# PCB-E21-CMB6_v03-17.net
KiCad netlist of a schematic drawn in EAGLE
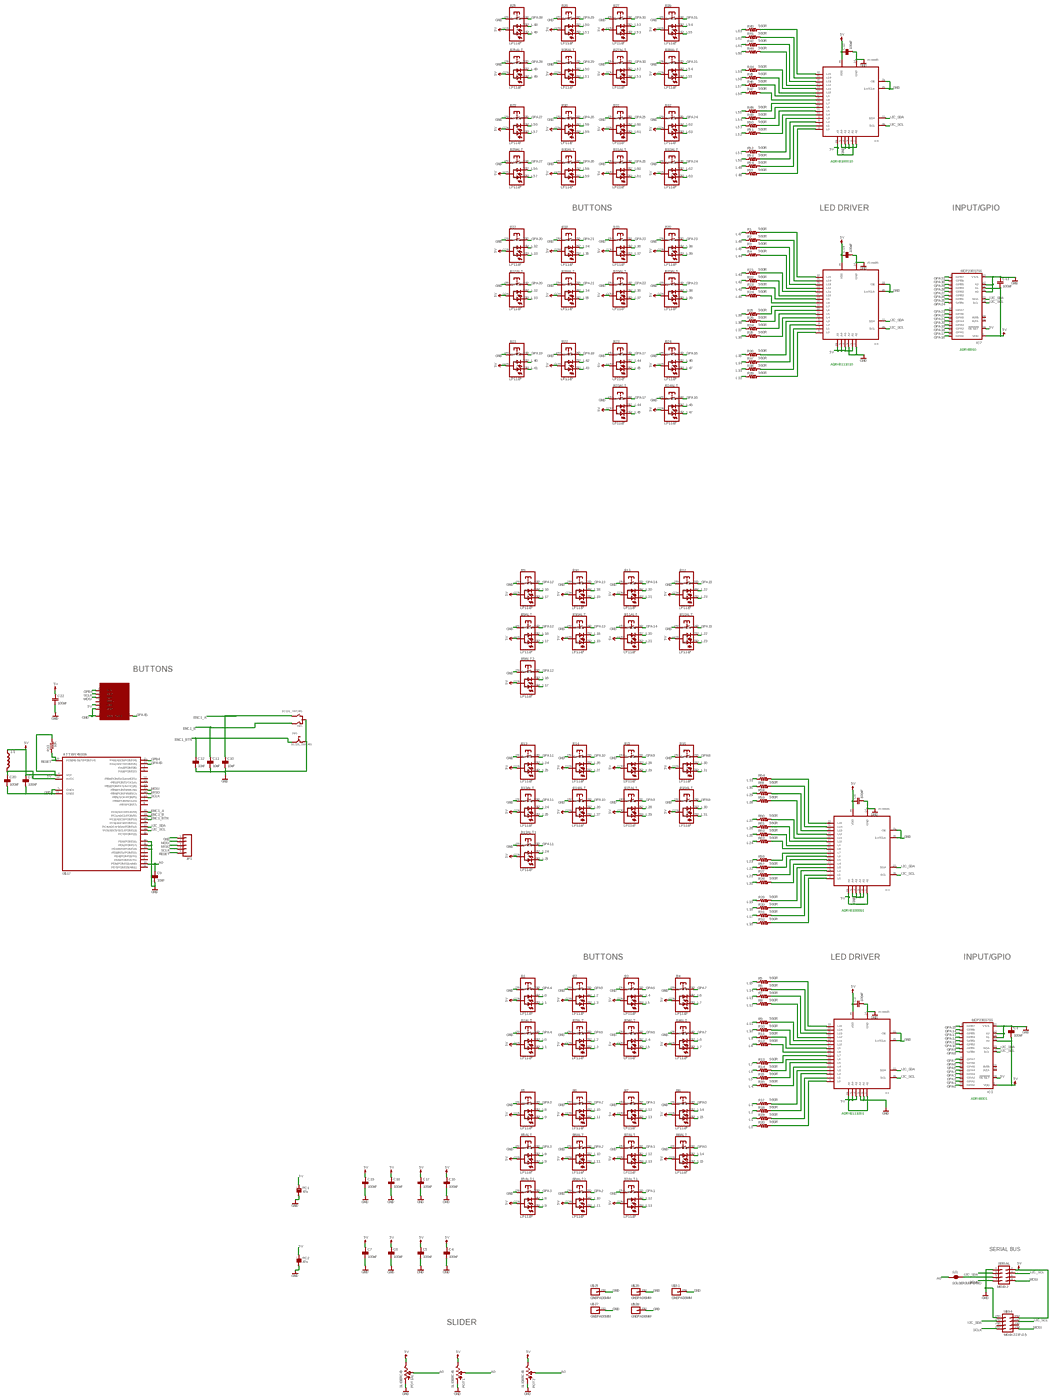
[diagram p0: schematic, sheet 1, overview]
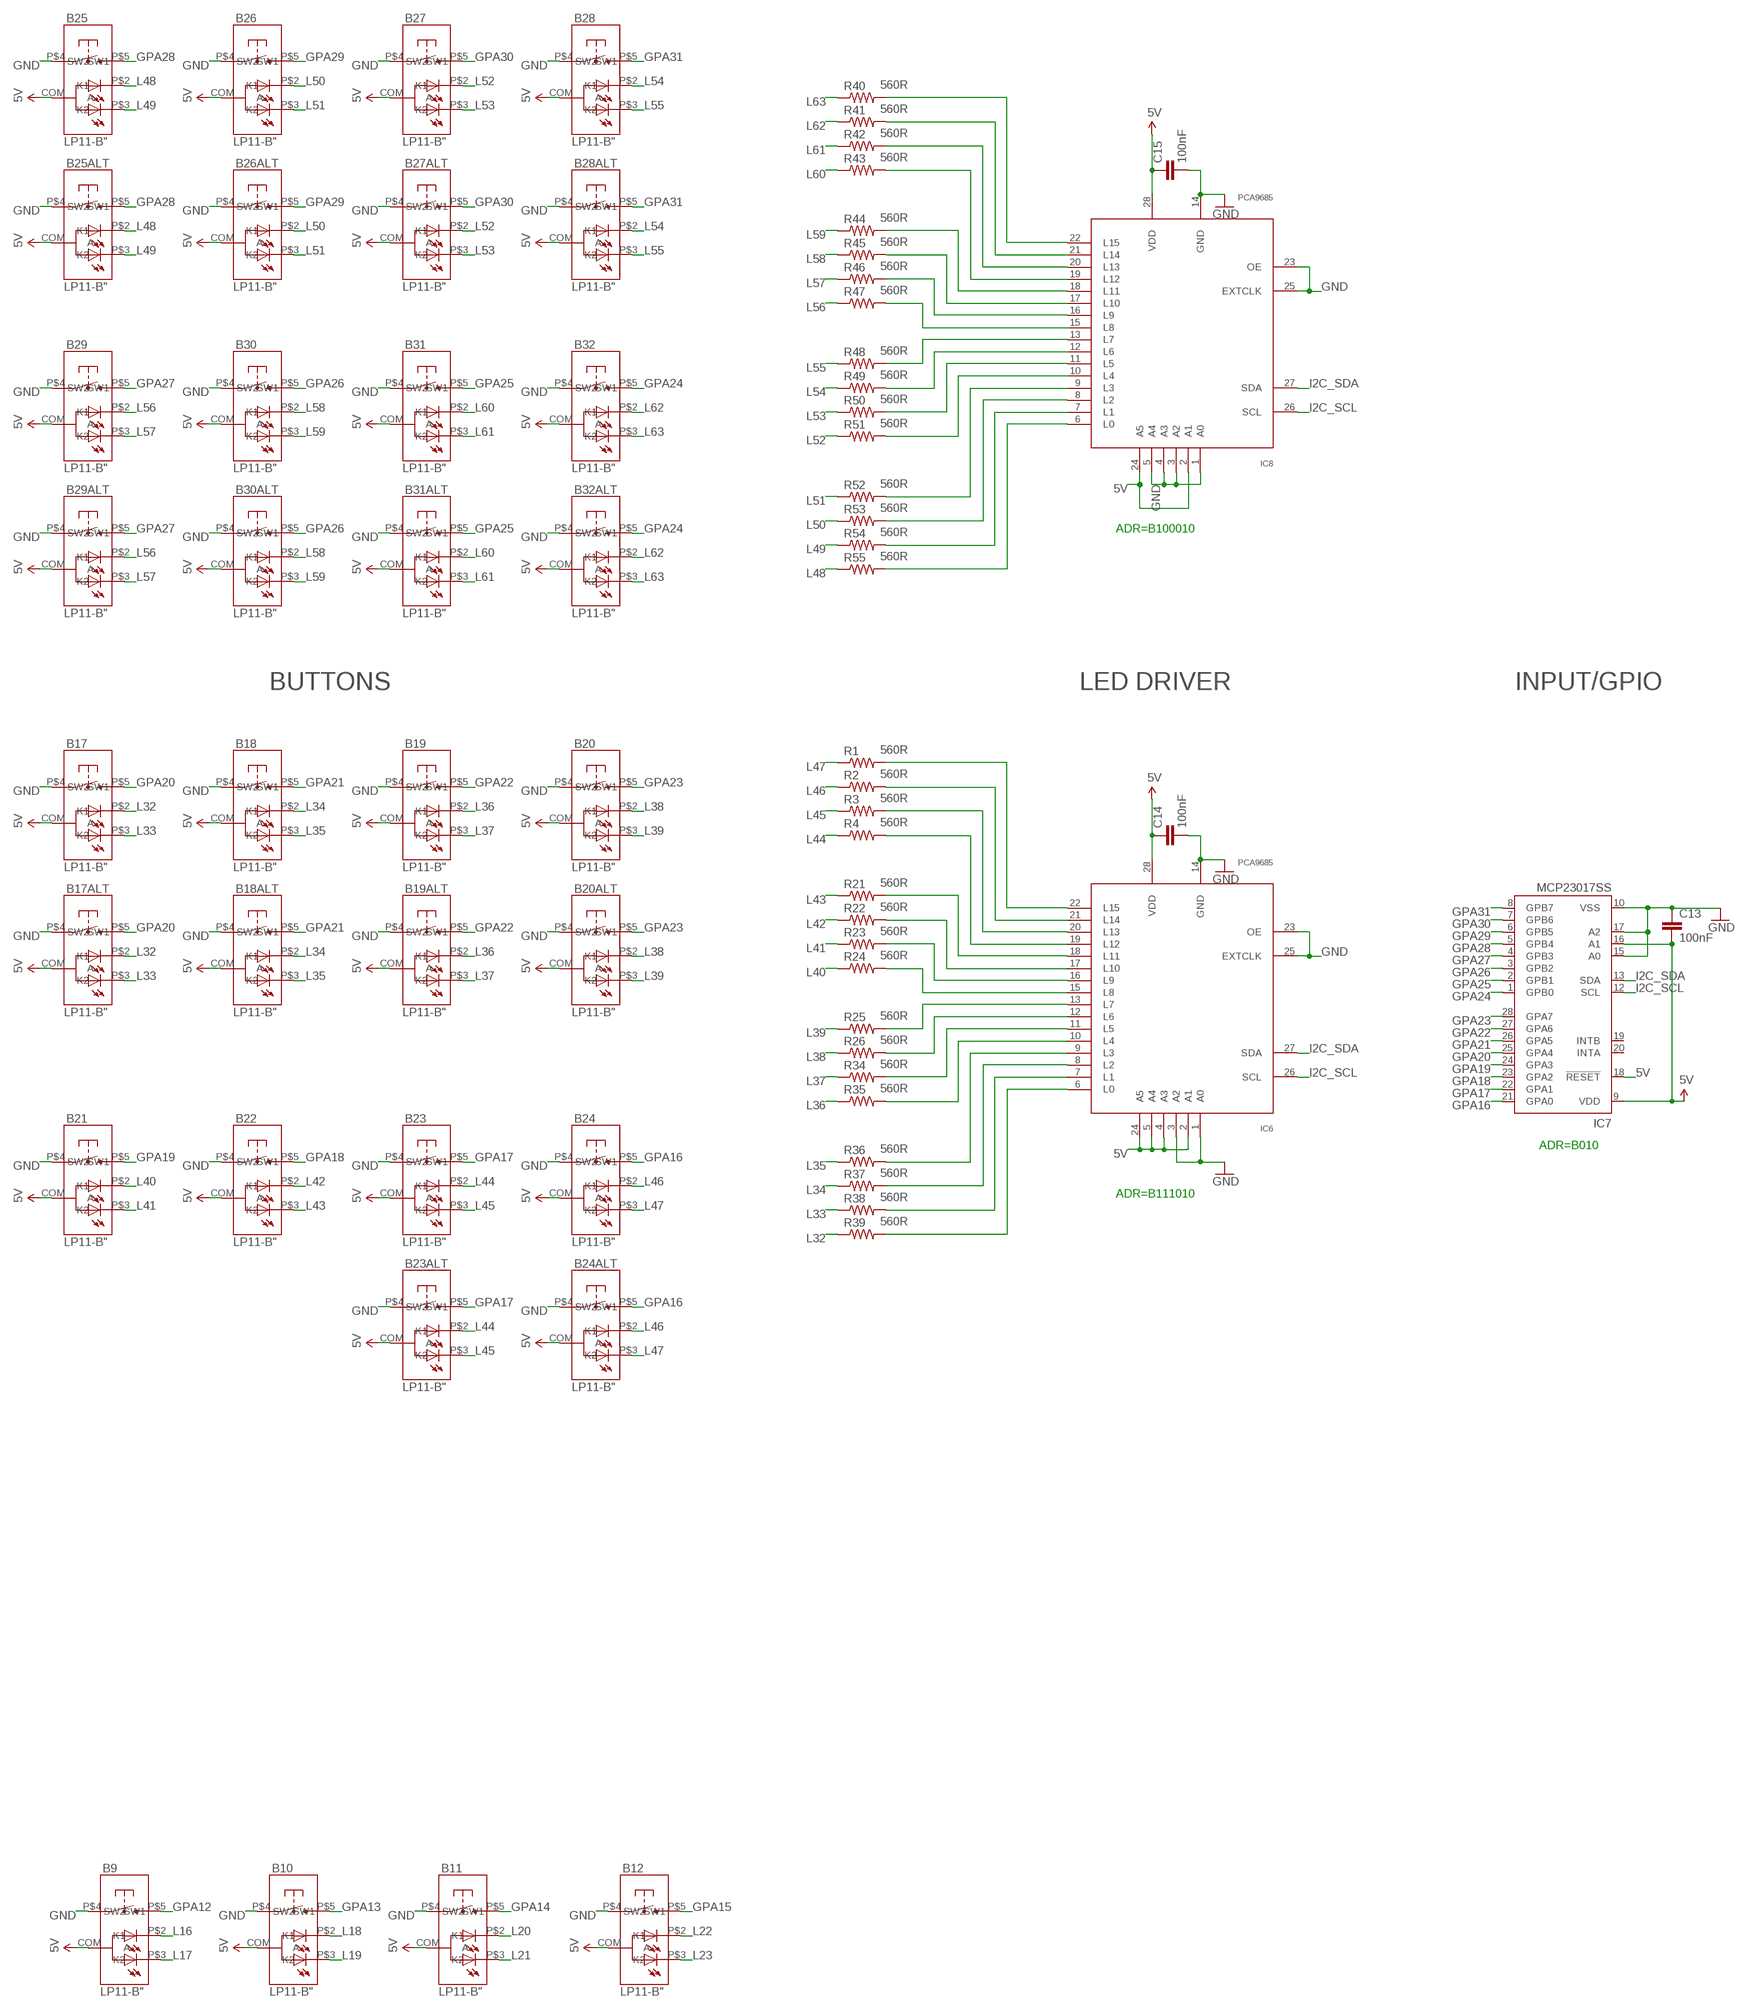
[diagram p1: schematic, sheet 1, part 1 of 5]
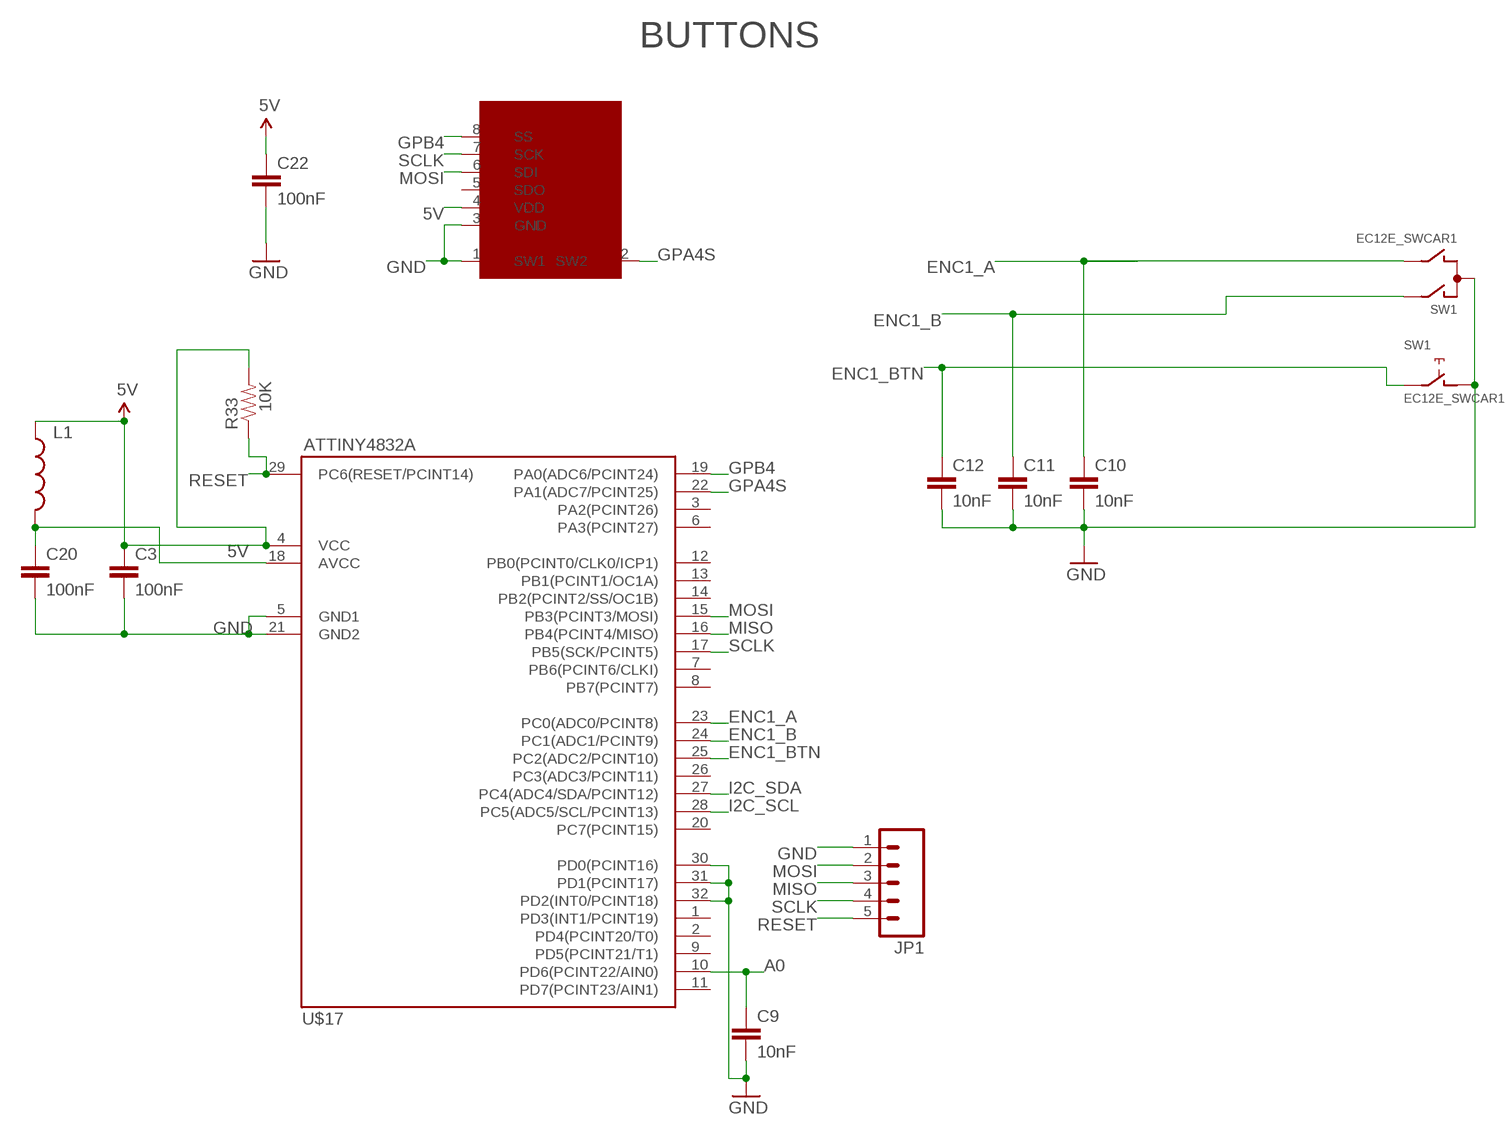
[diagram p2: schematic, sheet 1, part 2 of 5]
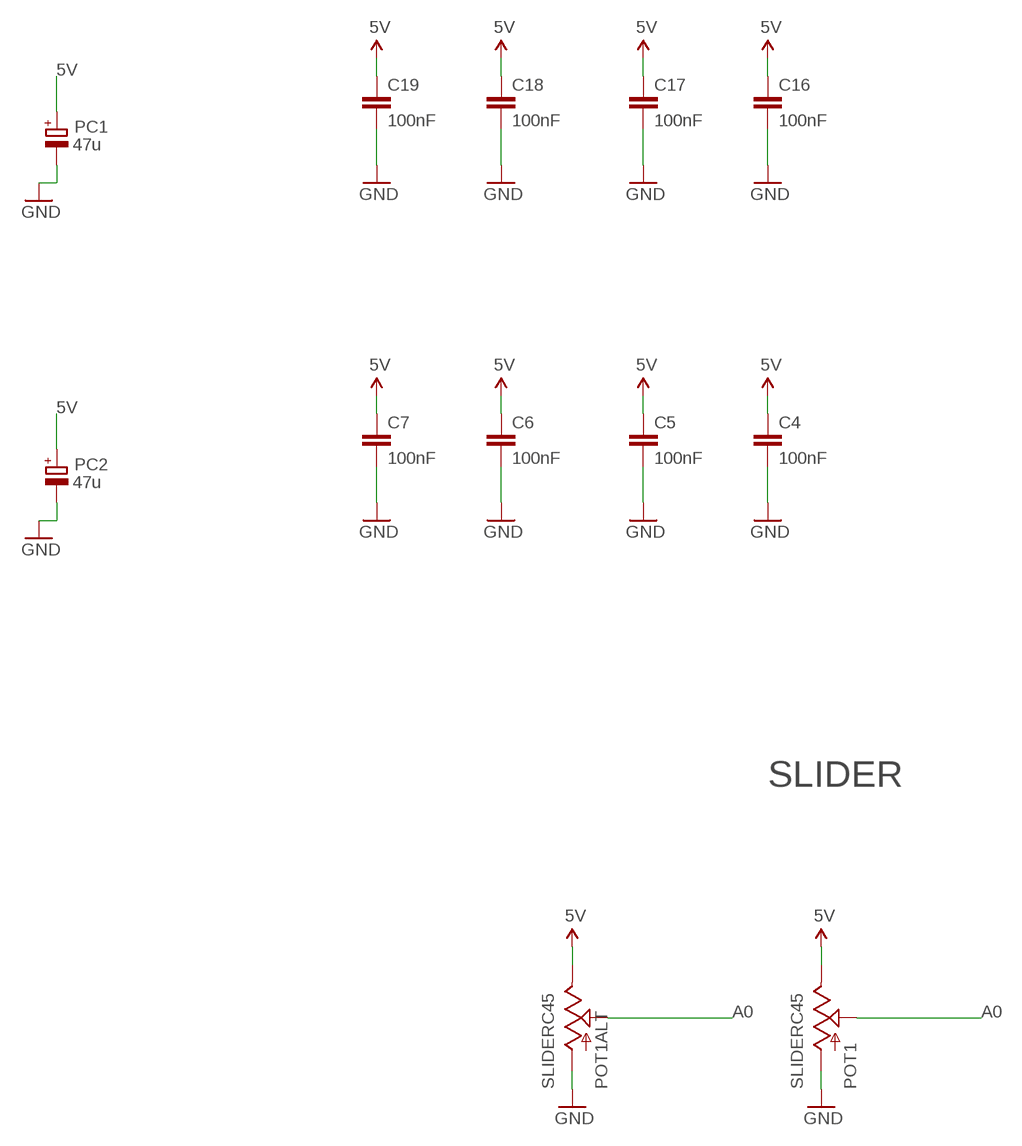
[diagram p3: schematic, sheet 1, part 3 of 5]
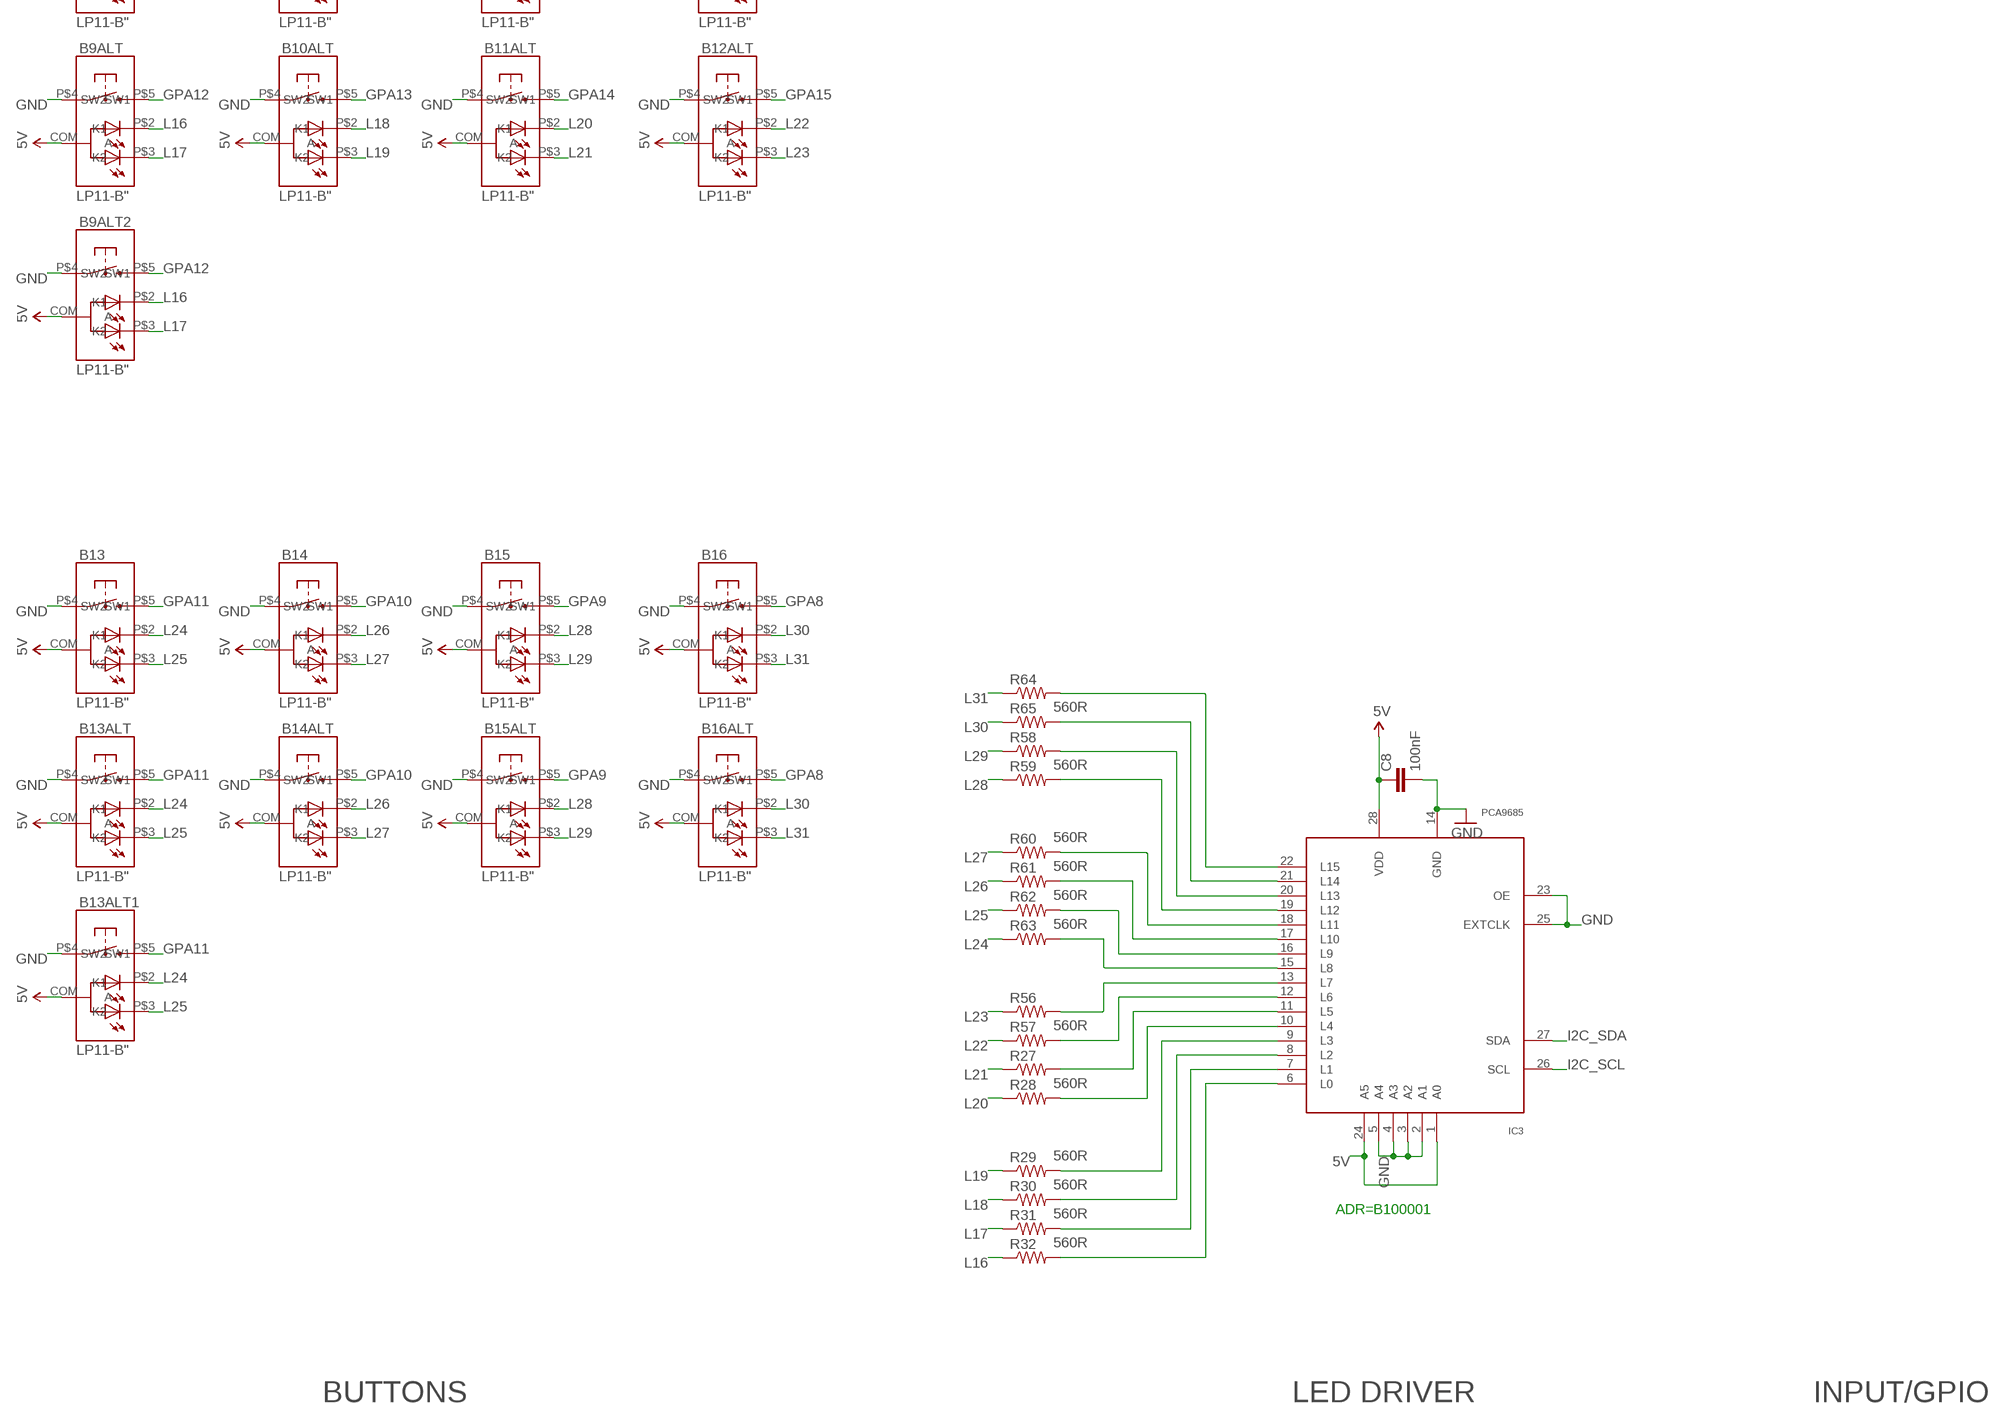
[diagram p4: schematic, sheet 1, part 4 of 5]
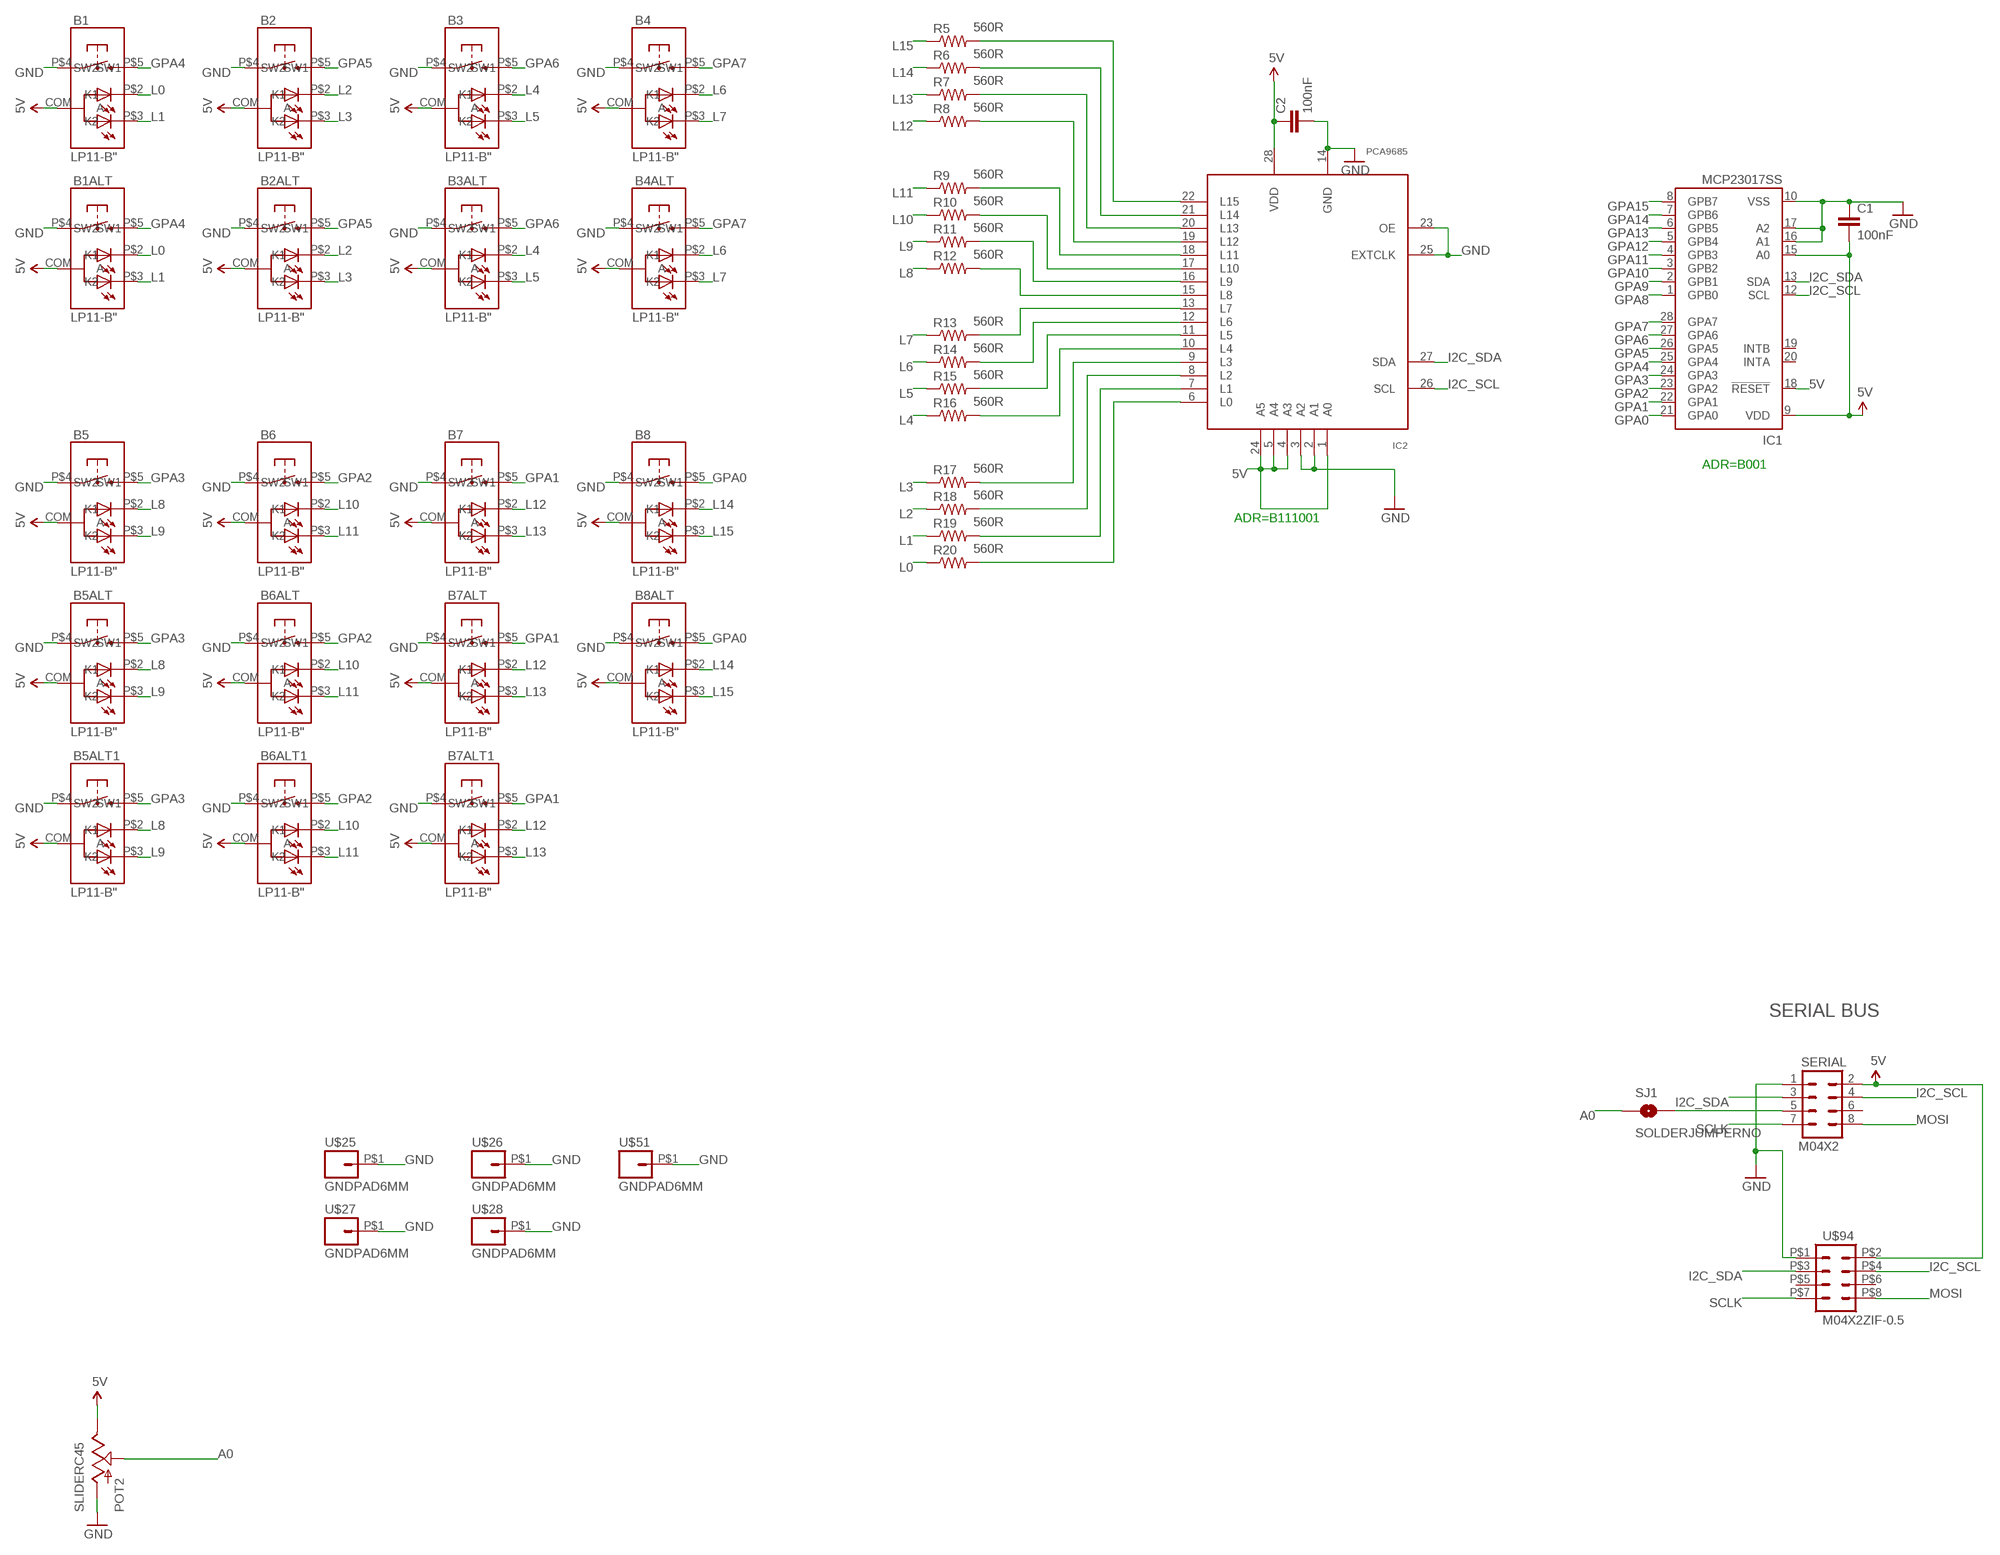
[diagram p5: schematic, sheet 1, part 5 of 5]

(export (version "E")
  (design (tool "Eeschema 10.0.6"))
  (components
    (comp (ref "B1")
      (value "LP11-B\"")
      (footprint "eagle-import:LP11")
      (libsource (lib "eagle-import") (part "LP11-B{dblquote}"))
    )
    (comp (ref "B1ALT")
      (value "LP11-B\"")
      (footprint "eagle-import:LP11")
      (libsource (lib "eagle-import") (part "LP11-B{dblquote}"))
    )
    (comp (ref "B2")
      (value "LP11-B\"")
      (footprint "eagle-import:LP11")
      (libsource (lib "eagle-import") (part "LP11-B{dblquote}"))
    )
    (comp (ref "B2ALT")
      (value "LP11-B\"")
      (footprint "eagle-import:LP11")
      (libsource (lib "eagle-import") (part "LP11-B{dblquote}"))
    )
    (comp (ref "B3")
      (value "LP11-B\"")
      (footprint "eagle-import:LP11")
      (libsource (lib "eagle-import") (part "LP11-B{dblquote}"))
    )
    (comp (ref "B3ALT")
      (value "LP11-B\"")
      (footprint "eagle-import:LP11")
      (libsource (lib "eagle-import") (part "LP11-B{dblquote}"))
    )
    (comp (ref "B4")
      (value "LP11-B\"")
      (footprint "eagle-import:LP11")
      (libsource (lib "eagle-import") (part "LP11-B{dblquote}"))
    )
    (comp (ref "B4ALT")
      (value "LP11-B\"")
      (footprint "eagle-import:LP11")
      (libsource (lib "eagle-import") (part "LP11-B{dblquote}"))
    )
    (comp (ref "B5")
      (value "LP11-B\"")
      (footprint "eagle-import:LP11")
      (libsource (lib "eagle-import") (part "LP11-B{dblquote}"))
    )
    (comp (ref "B5ALT")
      (value "LP11-B\"")
      (footprint "eagle-import:LP11")
      (libsource (lib "eagle-import") (part "LP11-B{dblquote}"))
    )
    (comp (ref "B5ALT1")
      (value "LP11-B\"")
      (footprint "eagle-import:LP11")
      (libsource (lib "eagle-import") (part "LP11-B{dblquote}"))
    )
    (comp (ref "B6")
      (value "LP11-B\"")
      (footprint "eagle-import:LP11")
      (libsource (lib "eagle-import") (part "LP11-B{dblquote}"))
    )
    (comp (ref "B6ALT")
      (value "LP11-B\"")
      (footprint "eagle-import:LP11")
      (libsource (lib "eagle-import") (part "LP11-B{dblquote}"))
    )
    (comp (ref "B6ALT1")
      (value "LP11-B\"")
      (footprint "eagle-import:LP11")
      (libsource (lib "eagle-import") (part "LP11-B{dblquote}"))
    )
    (comp (ref "B7")
      (value "LP11-B\"")
      (footprint "eagle-import:LP11")
      (libsource (lib "eagle-import") (part "LP11-B{dblquote}"))
    )
    (comp (ref "B7ALT")
      (value "LP11-B\"")
      (footprint "eagle-import:LP11")
      (libsource (lib "eagle-import") (part "LP11-B{dblquote}"))
    )
    (comp (ref "B7ALT1")
      (value "LP11-B\"")
      (footprint "eagle-import:LP11")
      (libsource (lib "eagle-import") (part "LP11-B{dblquote}"))
    )
    (comp (ref "B8")
      (value "LP11-B\"")
      (footprint "eagle-import:LP11")
      (libsource (lib "eagle-import") (part "LP11-B{dblquote}"))
    )
    (comp (ref "B8ALT")
      (value "LP11-B\"")
      (footprint "eagle-import:LP11")
      (libsource (lib "eagle-import") (part "LP11-B{dblquote}"))
    )
    (comp (ref "B9")
      (value "LP11-B\"")
      (footprint "eagle-import:LP11")
      (libsource (lib "eagle-import") (part "LP11-B{dblquote}"))
    )
    (comp (ref "B9ALT")
      (value "LP11-B\"")
      (footprint "eagle-import:LP11")
      (libsource (lib "eagle-import") (part "LP11-B{dblquote}"))
    )
    (comp (ref "B9ALT2")
      (value "LP11-B\"")
      (footprint "eagle-import:LP11")
      (libsource (lib "eagle-import") (part "LP11-B{dblquote}"))
    )
    (comp (ref "B10")
      (value "LP11-B\"")
      (footprint "eagle-import:LP11")
      (libsource (lib "eagle-import") (part "LP11-B{dblquote}"))
    )
    (comp (ref "B10ALT")
      (value "LP11-B\"")
      (footprint "eagle-import:LP11")
      (libsource (lib "eagle-import") (part "LP11-B{dblquote}"))
    )
    (comp (ref "B11")
      (value "LP11-B\"")
      (footprint "eagle-import:LP11")
      (libsource (lib "eagle-import") (part "LP11-B{dblquote}"))
    )
    (comp (ref "B11ALT")
      (value "LP11-B\"")
      (footprint "eagle-import:LP11")
      (libsource (lib "eagle-import") (part "LP11-B{dblquote}"))
    )
    (comp (ref "B12")
      (value "LP11-B\"")
      (footprint "eagle-import:LP11")
      (libsource (lib "eagle-import") (part "LP11-B{dblquote}"))
    )
    (comp (ref "B12ALT")
      (value "LP11-B\"")
      (footprint "eagle-import:LP11")
      (libsource (lib "eagle-import") (part "LP11-B{dblquote}"))
    )
    (comp (ref "B13")
      (value "LP11-B\"")
      (footprint "eagle-import:LP11")
      (libsource (lib "eagle-import") (part "LP11-B{dblquote}"))
    )
    (comp (ref "B13ALT")
      (value "LP11-B\"")
      (footprint "eagle-import:LP11")
      (libsource (lib "eagle-import") (part "LP11-B{dblquote}"))
    )
    (comp (ref "B13ALT1")
      (value "LP11-B\"")
      (footprint "eagle-import:LP11")
      (libsource (lib "eagle-import") (part "LP11-B{dblquote}"))
    )
    (comp (ref "B14")
      (value "LP11-B\"")
      (footprint "eagle-import:LP11")
      (libsource (lib "eagle-import") (part "LP11-B{dblquote}"))
    )
    (comp (ref "B14ALT")
      (value "LP11-B\"")
      (footprint "eagle-import:LP11")
      (libsource (lib "eagle-import") (part "LP11-B{dblquote}"))
    )
    (comp (ref "B15")
      (value "LP11-B\"")
      (footprint "eagle-import:LP11")
      (libsource (lib "eagle-import") (part "LP11-B{dblquote}"))
    )
    (comp (ref "B15ALT")
      (value "LP11-B\"")
      (footprint "eagle-import:LP11")
      (libsource (lib "eagle-import") (part "LP11-B{dblquote}"))
    )
    (comp (ref "B16")
      (value "LP11-B\"")
      (footprint "eagle-import:LP11")
      (libsource (lib "eagle-import") (part "LP11-B{dblquote}"))
    )
    (comp (ref "B16ALT")
      (value "LP11-B\"")
      (footprint "eagle-import:LP11")
      (libsource (lib "eagle-import") (part "LP11-B{dblquote}"))
    )
    (comp (ref "B17")
      (value "LP11-B\"")
      (footprint "eagle-import:LP11")
      (libsource (lib "eagle-import") (part "LP11-B{dblquote}"))
    )
    (comp (ref "B17ALT")
      (value "LP11-B\"")
      (footprint "eagle-import:LP11")
      (libsource (lib "eagle-import") (part "LP11-B{dblquote}"))
    )
    (comp (ref "B18")
      (value "LP11-B\"")
      (footprint "eagle-import:LP11")
      (libsource (lib "eagle-import") (part "LP11-B{dblquote}"))
    )
    (comp (ref "B18ALT")
      (value "LP11-B\"")
      (footprint "eagle-import:LP11")
      (libsource (lib "eagle-import") (part "LP11-B{dblquote}"))
    )
    (comp (ref "B19")
      (value "LP11-B\"")
      (footprint "eagle-import:LP11")
      (libsource (lib "eagle-import") (part "LP11-B{dblquote}"))
    )
    (comp (ref "B19ALT")
      (value "LP11-B\"")
      (footprint "eagle-import:LP11")
      (libsource (lib "eagle-import") (part "LP11-B{dblquote}"))
    )
    (comp (ref "B20")
      (value "LP11-B\"")
      (footprint "eagle-import:LP11")
      (libsource (lib "eagle-import") (part "LP11-B{dblquote}"))
    )
    (comp (ref "B20ALT")
      (value "LP11-B\"")
      (footprint "eagle-import:LP11")
      (libsource (lib "eagle-import") (part "LP11-B{dblquote}"))
    )
    (comp (ref "B21")
      (value "LP11-B\"")
      (footprint "eagle-import:LP11")
      (libsource (lib "eagle-import") (part "LP11-B{dblquote}"))
    )
    (comp (ref "B22")
      (value "LP11-B\"")
      (footprint "eagle-import:LP11")
      (libsource (lib "eagle-import") (part "LP11-B{dblquote}"))
    )
    (comp (ref "B23")
      (value "LP11-B\"")
      (footprint "eagle-import:LP11")
      (libsource (lib "eagle-import") (part "LP11-B{dblquote}"))
    )
    (comp (ref "B23ALT")
      (value "LP11-B\"")
      (footprint "eagle-import:LP11")
      (libsource (lib "eagle-import") (part "LP11-B{dblquote}"))
    )
    (comp (ref "B24")
      (value "LP11-B\"")
      (footprint "eagle-import:LP11")
      (libsource (lib "eagle-import") (part "LP11-B{dblquote}"))
    )
    (comp (ref "B24ALT")
      (value "LP11-B\"")
      (footprint "eagle-import:LP11")
      (libsource (lib "eagle-import") (part "LP11-B{dblquote}"))
    )
    (comp (ref "B25")
      (value "LP11-B\"")
      (footprint "eagle-import:LP11")
      (libsource (lib "eagle-import") (part "LP11-B{dblquote}"))
    )
    (comp (ref "B25ALT")
      (value "LP11-B\"")
      (footprint "eagle-import:LP11")
      (libsource (lib "eagle-import") (part "LP11-B{dblquote}"))
    )
    (comp (ref "B26")
      (value "LP11-B\"")
      (footprint "eagle-import:LP11")
      (libsource (lib "eagle-import") (part "LP11-B{dblquote}"))
    )
    (comp (ref "B26ALT")
      (value "LP11-B\"")
      (footprint "eagle-import:LP11")
      (libsource (lib "eagle-import") (part "LP11-B{dblquote}"))
    )
    (comp (ref "B27")
      (value "LP11-B\"")
      (footprint "eagle-import:LP11")
      (libsource (lib "eagle-import") (part "LP11-B{dblquote}"))
    )
    (comp (ref "B27ALT")
      (value "LP11-B\"")
      (footprint "eagle-import:LP11")
      (libsource (lib "eagle-import") (part "LP11-B{dblquote}"))
    )
    (comp (ref "B28")
      (value "LP11-B\"")
      (footprint "eagle-import:LP11")
      (libsource (lib "eagle-import") (part "LP11-B{dblquote}"))
    )
    (comp (ref "B28ALT")
      (value "LP11-B\"")
      (footprint "eagle-import:LP11")
      (libsource (lib "eagle-import") (part "LP11-B{dblquote}"))
    )
    (comp (ref "B29")
      (value "LP11-B\"")
      (footprint "eagle-import:LP11")
      (libsource (lib "eagle-import") (part "LP11-B{dblquote}"))
    )
    (comp (ref "B29ALT")
      (value "LP11-B\"")
      (footprint "eagle-import:LP11")
      (libsource (lib "eagle-import") (part "LP11-B{dblquote}"))
    )
    (comp (ref "B30")
      (value "LP11-B\"")
      (footprint "eagle-import:LP11")
      (libsource (lib "eagle-import") (part "LP11-B{dblquote}"))
    )
    (comp (ref "B30ALT")
      (value "LP11-B\"")
      (footprint "eagle-import:LP11")
      (libsource (lib "eagle-import") (part "LP11-B{dblquote}"))
    )
    (comp (ref "B31")
      (value "LP11-B\"")
      (footprint "eagle-import:LP11")
      (libsource (lib "eagle-import") (part "LP11-B{dblquote}"))
    )
    (comp (ref "B31ALT")
      (value "LP11-B\"")
      (footprint "eagle-import:LP11")
      (libsource (lib "eagle-import") (part "LP11-B{dblquote}"))
    )
    (comp (ref "B32")
      (value "LP11-B\"")
      (footprint "eagle-import:LP11")
      (libsource (lib "eagle-import") (part "LP11-B{dblquote}"))
    )
    (comp (ref "B32ALT")
      (value "LP11-B\"")
      (footprint "eagle-import:LP11")
      (libsource (lib "eagle-import") (part "LP11-B{dblquote}"))
    )
    (comp (ref "C1")
      (value "100nF")
      (footprint "eagle-import:0603-CAP")
      (libsource (lib "eagle-import") (part "CAP0603-CAP"))
    )
    (comp (ref "C2")
      (value "100nF")
      (footprint "eagle-import:0603-CAP")
      (libsource (lib "eagle-import") (part "CAP0603-CAP"))
    )
    (comp (ref "C3")
      (value "100nF")
      (footprint "eagle-import:0603-CAP")
      (libsource (lib "eagle-import") (part "CAP0603-CAP"))
    )
    (comp (ref "C4")
      (value "100nF")
      (footprint "eagle-import:0603-CAP")
      (libsource (lib "eagle-import") (part "CAP0603-CAP"))
    )
    (comp (ref "C5")
      (value "100nF")
      (footprint "eagle-import:0603-CAP")
      (libsource (lib "eagle-import") (part "CAP0603-CAP"))
    )
    (comp (ref "C6")
      (value "100nF")
      (footprint "eagle-import:0603-CAP")
      (libsource (lib "eagle-import") (part "CAP0603-CAP"))
    )
    (comp (ref "C7")
      (value "100nF")
      (footprint "eagle-import:0603-CAP")
      (libsource (lib "eagle-import") (part "CAP0603-CAP"))
    )
    (comp (ref "C8")
      (value "100nF")
      (footprint "eagle-import:0603-CAP")
      (libsource (lib "eagle-import") (part "CAP0603-CAP"))
    )
    (comp (ref "C9")
      (value "10nF")
      (footprint "eagle-import:0603-CAP")
      (libsource (lib "eagle-import") (part "CAP0603-CAP"))
    )
    (comp (ref "C10")
      (value "10nF")
      (footprint "eagle-import:0603-CAP")
      (libsource (lib "eagle-import") (part "CAP0603-CAP"))
    )
    (comp (ref "C11")
      (value "10nF")
      (footprint "eagle-import:0603-CAP")
      (libsource (lib "eagle-import") (part "CAP0603-CAP"))
    )
    (comp (ref "C12")
      (value "10nF")
      (footprint "eagle-import:0603-CAP")
      (libsource (lib "eagle-import") (part "CAP0603-CAP"))
    )
    (comp (ref "C13")
      (value "100nF")
      (footprint "eagle-import:0603-CAP")
      (libsource (lib "eagle-import") (part "CAP0603-CAP"))
    )
    (comp (ref "C14")
      (value "100nF")
      (footprint "eagle-import:0603-CAP")
      (libsource (lib "eagle-import") (part "CAP0603-CAP"))
    )
    (comp (ref "C15")
      (value "100nF")
      (footprint "eagle-import:0603-CAP")
      (libsource (lib "eagle-import") (part "CAP0603-CAP"))
    )
    (comp (ref "C16")
      (value "100nF")
      (footprint "eagle-import:0603-CAP")
      (libsource (lib "eagle-import") (part "CAP0603-CAP"))
    )
    (comp (ref "C17")
      (value "100nF")
      (footprint "eagle-import:0603-CAP")
      (libsource (lib "eagle-import") (part "CAP0603-CAP"))
    )
    (comp (ref "C18")
      (value "100nF")
      (footprint "eagle-import:0603-CAP")
      (libsource (lib "eagle-import") (part "CAP0603-CAP"))
    )
    (comp (ref "C19")
      (value "100nF")
      (footprint "eagle-import:0603-CAP")
      (libsource (lib "eagle-import") (part "CAP0603-CAP"))
    )
    (comp (ref "C20")
      (value "100nF")
      (footprint "eagle-import:0603-CAP")
      (libsource (lib "eagle-import") (part "CAP0603-CAP"))
    )
    (comp (ref "C22")
      (value "100nF")
      (footprint "eagle-import:0603-CAP")
      (libsource (lib "eagle-import") (part "CAP0603-CAP"))
    )
    (comp (ref "IC1")
      (value "MCP23017SS")
      (footprint "eagle-import:SSOP28")
      (fields
        (field (name "MF") "MICROCHIP")
        (field (name "MPN") "MCP23017-E/SS")
        (field (name "MPN_1") "MCP23017-E/SS")
        (field (name "OC_FARNELL") "1467674")
        (field (name "OC_NEWARK") "31K2960")
      )
      (libsource (lib "eagle-import") (part "MCP23017SS"))
    )
    (comp (ref "IC2")
      (value "PCA9685")
      (footprint "eagle-import:TSSOP28")
      (libsource (lib "eagle-import") (part "PCA9685"))
    )
    (comp (ref "IC3")
      (value "PCA9685")
      (footprint "eagle-import:TSSOP28")
      (libsource (lib "eagle-import") (part "PCA9685"))
    )
    (comp (ref "IC6")
      (value "PCA9685")
      (footprint "eagle-import:TSSOP28")
      (libsource (lib "eagle-import") (part "PCA9685"))
    )
    (comp (ref "IC7")
      (value "MCP23017SS")
      (footprint "eagle-import:SSOP28")
      (fields
        (field (name "MF") "MICROCHIP")
        (field (name "MPN") "MCP23017-E/SS")
        (field (name "MPN_1") "MCP23017-E/SS")
        (field (name "OC_FARNELL") "1467674")
        (field (name "OC_NEWARK") "31K2960")
      )
      (libsource (lib "eagle-import") (part "MCP23017SS"))
    )
    (comp (ref "IC8")
      (value "PCA9685")
      (footprint "eagle-import:TSSOP28")
      (libsource (lib "eagle-import") (part "PCA9685"))
    )
    (comp (ref "JP1")
      (value "M051.27MM")
      (footprint "eagle-import:1X05-1.27MM")
      (libsource (lib "eagle-import") (part "M051.27MM"))
    )
    (comp (ref "L1")
      (value "INDUCTOR0805")
      (footprint "eagle-import:0805")
      (libsource (lib "eagle-import") (part "INDUCTOR0805"))
    )
    (comp (ref "PC1")
      (value "47u")
      (footprint "eagle-import:PANASONIC_D")
      (libsource (lib "eagle-import") (part "CPOL-EUD"))
    )
    (comp (ref "PC2")
      (value "47u")
      (footprint "eagle-import:PANASONIC_D")
      (libsource (lib "eagle-import") (part "CPOL-EUD"))
    )
    (comp (ref "POT1")
      (value "SLIDERC45")
      (footprint "eagle-import:SLIDER45-CAR1")
      (libsource (lib "eagle-import") (part "SLIDERC45"))
    )
    (comp (ref "POT1ALT")
      (value "SLIDERC45")
      (footprint "eagle-import:SLIDER45-CAR1")
      (libsource (lib "eagle-import") (part "SLIDERC45"))
    )
    (comp (ref "POT2")
      (value "SLIDERC45")
      (footprint "eagle-import:SLIDER45-CAR1")
      (libsource (lib "eagle-import") (part "SLIDERC45"))
    )
    (comp (ref "R1")
      (value "560R")
      (footprint "eagle-import:0603-RES")
      (libsource (lib "eagle-import") (part "RESISTOR0603-RES"))
    )
    (comp (ref "R2")
      (value "560R")
      (footprint "eagle-import:0603-RES")
      (libsource (lib "eagle-import") (part "RESISTOR0603-RES"))
    )
    (comp (ref "R3")
      (value "560R")
      (footprint "eagle-import:0603-RES")
      (libsource (lib "eagle-import") (part "RESISTOR0603-RES"))
    )
    (comp (ref "R4")
      (value "560R")
      (footprint "eagle-import:0603-RES")
      (libsource (lib "eagle-import") (part "RESISTOR0603-RES"))
    )
    (comp (ref "R5")
      (value "560R")
      (footprint "eagle-import:0603-RES")
      (libsource (lib "eagle-import") (part "RESISTOR0603-RES"))
    )
    (comp (ref "R6")
      (value "560R")
      (footprint "eagle-import:0603-RES")
      (libsource (lib "eagle-import") (part "RESISTOR0603-RES"))
    )
    (comp (ref "R7")
      (value "560R")
      (footprint "eagle-import:0603-RES")
      (libsource (lib "eagle-import") (part "RESISTOR0603-RES"))
    )
    (comp (ref "R8")
      (value "560R")
      (footprint "eagle-import:0603-RES")
      (libsource (lib "eagle-import") (part "RESISTOR0603-RES"))
    )
    (comp (ref "R9")
      (value "560R")
      (footprint "eagle-import:0603-RES")
      (libsource (lib "eagle-import") (part "RESISTOR0603-RES"))
    )
    (comp (ref "R10")
      (value "560R")
      (footprint "eagle-import:0603-RES")
      (libsource (lib "eagle-import") (part "RESISTOR0603-RES"))
    )
    (comp (ref "R11")
      (value "560R")
      (footprint "eagle-import:0603-RES")
      (libsource (lib "eagle-import") (part "RESISTOR0603-RES"))
    )
    (comp (ref "R12")
      (value "560R")
      (footprint "eagle-import:0603-RES")
      (libsource (lib "eagle-import") (part "RESISTOR0603-RES"))
    )
    (comp (ref "R13")
      (value "560R")
      (footprint "eagle-import:0603-RES")
      (libsource (lib "eagle-import") (part "RESISTOR0603-RES"))
    )
    (comp (ref "R14")
      (value "560R")
      (footprint "eagle-import:0603-RES")
      (libsource (lib "eagle-import") (part "RESISTOR0603-RES"))
    )
    (comp (ref "R15")
      (value "560R")
      (footprint "eagle-import:0603-RES")
      (libsource (lib "eagle-import") (part "RESISTOR0603-RES"))
    )
    (comp (ref "R16")
      (value "560R")
      (footprint "eagle-import:0603-RES")
      (libsource (lib "eagle-import") (part "RESISTOR0603-RES"))
    )
    (comp (ref "R17")
      (value "560R")
      (footprint "eagle-import:0603-RES")
      (libsource (lib "eagle-import") (part "RESISTOR0603-RES"))
    )
    (comp (ref "R18")
      (value "560R")
      (footprint "eagle-import:0603-RES")
      (libsource (lib "eagle-import") (part "RESISTOR0603-RES"))
    )
    (comp (ref "R19")
      (value "560R")
      (footprint "eagle-import:0603-RES")
      (libsource (lib "eagle-import") (part "RESISTOR0603-RES"))
    )
    (comp (ref "R20")
      (value "560R")
      (footprint "eagle-import:0603-RES")
      (libsource (lib "eagle-import") (part "RESISTOR0603-RES"))
    )
    (comp (ref "R21")
      (value "560R")
      (footprint "eagle-import:0603-RES")
      (libsource (lib "eagle-import") (part "RESISTOR0603-RES"))
    )
    (comp (ref "R22")
      (value "560R")
      (footprint "eagle-import:0603-RES")
      (libsource (lib "eagle-import") (part "RESISTOR0603-RES"))
    )
    (comp (ref "R23")
      (value "560R")
      (footprint "eagle-import:0603-RES")
      (libsource (lib "eagle-import") (part "RESISTOR0603-RES"))
    )
    (comp (ref "R24")
      (value "560R")
      (footprint "eagle-import:0603-RES")
      (libsource (lib "eagle-import") (part "RESISTOR0603-RES"))
    )
    (comp (ref "R25")
      (value "560R")
      (footprint "eagle-import:0603-RES")
      (libsource (lib "eagle-import") (part "RESISTOR0603-RES"))
    )
    (comp (ref "R26")
      (value "560R")
      (footprint "eagle-import:0603-RES")
      (libsource (lib "eagle-import") (part "RESISTOR0603-RES"))
    )
    (comp (ref "R27")
      (value "560R")
      (footprint "eagle-import:0603-RES")
      (libsource (lib "eagle-import") (part "RESISTOR0603-RES"))
    )
    (comp (ref "R28")
      (value "560R")
      (footprint "eagle-import:0603-RES")
      (libsource (lib "eagle-import") (part "RESISTOR0603-RES"))
    )
    (comp (ref "R29")
      (value "560R")
      (footprint "eagle-import:0603-RES")
      (libsource (lib "eagle-import") (part "RESISTOR0603-RES"))
    )
    (comp (ref "R30")
      (value "560R")
      (footprint "eagle-import:0603-RES")
      (libsource (lib "eagle-import") (part "RESISTOR0603-RES"))
    )
    (comp (ref "R31")
      (value "560R")
      (footprint "eagle-import:0603-RES")
      (libsource (lib "eagle-import") (part "RESISTOR0603-RES"))
    )
    (comp (ref "R32")
      (value "560R")
      (footprint "eagle-import:0603-RES")
      (libsource (lib "eagle-import") (part "RESISTOR0603-RES"))
    )
    (comp (ref "R33")
      (value "10K")
      (footprint "eagle-import:0603-RES")
      (libsource (lib "eagle-import") (part "RESISTOR0603-RES"))
    )
    (comp (ref "R34")
      (value "560R")
      (footprint "eagle-import:0603-RES")
      (libsource (lib "eagle-import") (part "RESISTOR0603-RES"))
    )
    (comp (ref "R35")
      (value "560R")
      (footprint "eagle-import:0603-RES")
      (libsource (lib "eagle-import") (part "RESISTOR0603-RES"))
    )
    (comp (ref "R36")
      (value "560R")
      (footprint "eagle-import:0603-RES")
      (libsource (lib "eagle-import") (part "RESISTOR0603-RES"))
    )
    (comp (ref "R37")
      (value "560R")
      (footprint "eagle-import:0603-RES")
      (libsource (lib "eagle-import") (part "RESISTOR0603-RES"))
    )
    (comp (ref "R38")
      (value "560R")
      (footprint "eagle-import:0603-RES")
      (libsource (lib "eagle-import") (part "RESISTOR0603-RES"))
    )
    (comp (ref "R39")
      (value "560R")
      (footprint "eagle-import:0603-RES")
      (libsource (lib "eagle-import") (part "RESISTOR0603-RES"))
    )
    (comp (ref "R40")
      (value "560R")
      (footprint "eagle-import:0603-RES")
      (libsource (lib "eagle-import") (part "RESISTOR0603-RES"))
    )
    (comp (ref "R41")
      (value "560R")
      (footprint "eagle-import:0603-RES")
      (libsource (lib "eagle-import") (part "RESISTOR0603-RES"))
    )
    (comp (ref "R42")
      (value "560R")
      (footprint "eagle-import:0603-RES")
      (libsource (lib "eagle-import") (part "RESISTOR0603-RES"))
    )
    (comp (ref "R43")
      (value "560R")
      (footprint "eagle-import:0603-RES")
      (libsource (lib "eagle-import") (part "RESISTOR0603-RES"))
    )
    (comp (ref "R44")
      (value "560R")
      (footprint "eagle-import:0603-RES")
      (libsource (lib "eagle-import") (part "RESISTOR0603-RES"))
    )
    (comp (ref "R45")
      (value "560R")
      (footprint "eagle-import:0603-RES")
      (libsource (lib "eagle-import") (part "RESISTOR0603-RES"))
    )
    (comp (ref "R46")
      (value "560R")
      (footprint "eagle-import:0603-RES")
      (libsource (lib "eagle-import") (part "RESISTOR0603-RES"))
    )
    (comp (ref "R47")
      (value "560R")
      (footprint "eagle-import:0603-RES")
      (libsource (lib "eagle-import") (part "RESISTOR0603-RES"))
    )
    (comp (ref "R48")
      (value "560R")
      (footprint "eagle-import:0603-RES")
      (libsource (lib "eagle-import") (part "RESISTOR0603-RES"))
    )
    (comp (ref "R49")
      (value "560R")
      (footprint "eagle-import:0603-RES")
      (libsource (lib "eagle-import") (part "RESISTOR0603-RES"))
    )
    (comp (ref "R50")
      (value "560R")
      (footprint "eagle-import:0603-RES")
      (libsource (lib "eagle-import") (part "RESISTOR0603-RES"))
    )
    (comp (ref "R51")
      (value "560R")
      (footprint "eagle-import:0603-RES")
      (libsource (lib "eagle-import") (part "RESISTOR0603-RES"))
    )
    (comp (ref "R52")
      (value "560R")
      (footprint "eagle-import:0603-RES")
      (libsource (lib "eagle-import") (part "RESISTOR0603-RES"))
    )
    (comp (ref "R53")
      (value "560R")
      (footprint "eagle-import:0603-RES")
      (libsource (lib "eagle-import") (part "RESISTOR0603-RES"))
    )
    (comp (ref "R54")
      (value "560R")
      (footprint "eagle-import:0603-RES")
      (libsource (lib "eagle-import") (part "RESISTOR0603-RES"))
    )
    (comp (ref "R55")
      (value "560R")
      (footprint "eagle-import:0603-RES")
      (libsource (lib "eagle-import") (part "RESISTOR0603-RES"))
    )
    (comp (ref "R56")
      (value "560R")
      (footprint "eagle-import:0603-RES")
      (libsource (lib "eagle-import") (part "RESISTOR0603-RES"))
    )
    (comp (ref "R57")
      (value "560R")
      (footprint "eagle-import:0603-RES")
      (libsource (lib "eagle-import") (part "RESISTOR0603-RES"))
    )
    (comp (ref "R58")
      (value "560R")
      (footprint "eagle-import:0603-RES")
      (libsource (lib "eagle-import") (part "RESISTOR0603-RES"))
    )
    (comp (ref "R59")
      (value "560R")
      (footprint "eagle-import:0603-RES")
      (libsource (lib "eagle-import") (part "RESISTOR0603-RES"))
    )
    (comp (ref "R60")
      (value "560R")
      (footprint "eagle-import:0603-RES")
      (libsource (lib "eagle-import") (part "RESISTOR0603-RES"))
    )
    (comp (ref "R61")
      (value "560R")
      (footprint "eagle-import:0603-RES")
      (libsource (lib "eagle-import") (part "RESISTOR0603-RES"))
    )
    (comp (ref "R62")
      (value "560R")
      (footprint "eagle-import:0603-RES")
      (libsource (lib "eagle-import") (part "RESISTOR0603-RES"))
    )
    (comp (ref "R63")
      (value "560R")
      (footprint "eagle-import:0603-RES")
      (libsource (lib "eagle-import") (part "RESISTOR0603-RES"))
    )
    (comp (ref "R64")
      (value "560R")
      (footprint "eagle-import:0603-RES")
      (libsource (lib "eagle-import") (part "RESISTOR0603-RES"))
    )
    (comp (ref "R65")
      (value "560R")
      (footprint "eagle-import:0603-RES")
      (libsource (lib "eagle-import") (part "RESISTOR0603-RES"))
    )
    (comp (ref "SERIAL")
      (value "M04X2")
      (footprint "eagle-import:2X4")
      (libsource (lib "eagle-import") (part "SparkFun_M04X2"))
    )
    (comp (ref "SJ1")
      (value "SOLDERJUMPERNO")
      (footprint "eagle-import:SJ_2S-NO")
      (libsource (lib "eagle-import") (part "SOLDERJUMPERNO"))
    )
    (comp (ref "SSW1")
      (value "SMART_SWITCHSMART_SWITCH_8PIN")
      (footprint "eagle-import:SMART_SWITCH")
      (libsource (lib "eagle-import") (part "SMART_SWITCHSMART_SWITCH_8PIN"))
    )
    (comp (ref "SW1")
      (value "EC12E_SWCAR1")
      (footprint "eagle-import:ALPS_EC12E_SW-CAR1")
      (libsource (lib "eagle-import") (part "EC12E_SWCAR1"))
    )
    (comp (ref "U$17")
      (value "ATTINY4832A")
      (footprint "eagle-import:TQFP32-08")
      (libsource (lib "eagle-import") (part "ATTINY4832A"))
    )
    (comp (ref "U$25")
      (value "GNDPAD6MM")
      (footprint "eagle-import:3.2MMPAD6MM")
      (libsource (lib "eagle-import") (part "GNDPAD6MM"))
    )
    (comp (ref "U$26")
      (value "GNDPAD6MM")
      (footprint "eagle-import:3.2MMPAD6MM")
      (libsource (lib "eagle-import") (part "GNDPAD6MM"))
    )
    (comp (ref "U$27")
      (value "GNDPAD6MM")
      (footprint "eagle-import:3.2MMPAD6MM")
      (libsource (lib "eagle-import") (part "GNDPAD6MM"))
    )
    (comp (ref "U$28")
      (value "GNDPAD6MM")
      (footprint "eagle-import:3.2MMPAD6MM")
      (libsource (lib "eagle-import") (part "GNDPAD6MM"))
    )
    (comp (ref "U$51")
      (value "GNDPAD6MM")
      (footprint "eagle-import:3.2MMPAD6MM")
      (libsource (lib "eagle-import") (part "GNDPAD6MM"))
    )
    (comp (ref "U$94")
      (value "M04X2ZIF-0.5")
      (footprint "eagle-import:ZIP-8-0.5")
      (libsource (lib "eagle-import") (part "M04X2ZIF-0.5"))
    )
  )
  (nets
    (net (code "1") (name "5V") (class "Default")
      (node (ref "B1") (pin "COM") (pinfunction "A_COM") (pintype "bidirectional"))
      (node (ref "B10") (pin "COM") (pinfunction "A_COM") (pintype "bidirectional"))
      (node (ref "B10ALT") (pin "COM") (pinfunction "A_COM") (pintype "bidirectional"))
      (node (ref "B11") (pin "COM") (pinfunction "A_COM") (pintype "bidirectional"))
      (node (ref "B11ALT") (pin "COM") (pinfunction "A_COM") (pintype "bidirectional"))
      (node (ref "B12") (pin "COM") (pinfunction "A_COM") (pintype "bidirectional"))
      (node (ref "B12ALT") (pin "COM") (pinfunction "A_COM") (pintype "bidirectional"))
      (node (ref "B13") (pin "COM") (pinfunction "A_COM") (pintype "bidirectional"))
      (node (ref "B13ALT") (pin "COM") (pinfunction "A_COM") (pintype "bidirectional"))
      (node (ref "B13ALT1") (pin "COM") (pinfunction "A_COM") (pintype "bidirectional"))
      (node (ref "B14") (pin "COM") (pinfunction "A_COM") (pintype "bidirectional"))
      (node (ref "B14ALT") (pin "COM") (pinfunction "A_COM") (pintype "bidirectional"))
      (node (ref "B15") (pin "COM") (pinfunction "A_COM") (pintype "bidirectional"))
      (node (ref "B15ALT") (pin "COM") (pinfunction "A_COM") (pintype "bidirectional"))
      (node (ref "B16") (pin "COM") (pinfunction "A_COM") (pintype "bidirectional"))
      (node (ref "B16ALT") (pin "COM") (pinfunction "A_COM") (pintype "bidirectional"))
      (node (ref "B17") (pin "COM") (pinfunction "A_COM") (pintype "bidirectional"))
      (node (ref "B17ALT") (pin "COM") (pinfunction "A_COM") (pintype "bidirectional"))
      (node (ref "B18") (pin "COM") (pinfunction "A_COM") (pintype "bidirectional"))
      (node (ref "B18ALT") (pin "COM") (pinfunction "A_COM") (pintype "bidirectional"))
      (node (ref "B19") (pin "COM") (pinfunction "A_COM") (pintype "bidirectional"))
      (node (ref "B19ALT") (pin "COM") (pinfunction "A_COM") (pintype "bidirectional"))
      (node (ref "B1ALT") (pin "COM") (pinfunction "A_COM") (pintype "bidirectional"))
      (node (ref "B2") (pin "COM") (pinfunction "A_COM") (pintype "bidirectional"))
      (node (ref "B20") (pin "COM") (pinfunction "A_COM") (pintype "bidirectional"))
      (node (ref "B20ALT") (pin "COM") (pinfunction "A_COM") (pintype "bidirectional"))
      (node (ref "B21") (pin "COM") (pinfunction "A_COM") (pintype "bidirectional"))
      (node (ref "B22") (pin "COM") (pinfunction "A_COM") (pintype "bidirectional"))
      (node (ref "B23") (pin "COM") (pinfunction "A_COM") (pintype "bidirectional"))
      (node (ref "B23ALT") (pin "COM") (pinfunction "A_COM") (pintype "bidirectional"))
      (node (ref "B24") (pin "COM") (pinfunction "A_COM") (pintype "bidirectional"))
      (node (ref "B24ALT") (pin "COM") (pinfunction "A_COM") (pintype "bidirectional"))
      (node (ref "B25") (pin "COM") (pinfunction "A_COM") (pintype "bidirectional"))
      (node (ref "B25ALT") (pin "COM") (pinfunction "A_COM") (pintype "bidirectional"))
      (node (ref "B26") (pin "COM") (pinfunction "A_COM") (pintype "bidirectional"))
      (node (ref "B26ALT") (pin "COM") (pinfunction "A_COM") (pintype "bidirectional"))
      (node (ref "B27") (pin "COM") (pinfunction "A_COM") (pintype "bidirectional"))
      (node (ref "B27ALT") (pin "COM") (pinfunction "A_COM") (pintype "bidirectional"))
      (node (ref "B28") (pin "COM") (pinfunction "A_COM") (pintype "bidirectional"))
      (node (ref "B28ALT") (pin "COM") (pinfunction "A_COM") (pintype "bidirectional"))
      (node (ref "B29") (pin "COM") (pinfunction "A_COM") (pintype "bidirectional"))
      (node (ref "B29ALT") (pin "COM") (pinfunction "A_COM") (pintype "bidirectional"))
      (node (ref "B2ALT") (pin "COM") (pinfunction "A_COM") (pintype "bidirectional"))
      (node (ref "B3") (pin "COM") (pinfunction "A_COM") (pintype "bidirectional"))
      (node (ref "B30") (pin "COM") (pinfunction "A_COM") (pintype "bidirectional"))
      (node (ref "B30ALT") (pin "COM") (pinfunction "A_COM") (pintype "bidirectional"))
      (node (ref "B31") (pin "COM") (pinfunction "A_COM") (pintype "bidirectional"))
      (node (ref "B31ALT") (pin "COM") (pinfunction "A_COM") (pintype "bidirectional"))
      (node (ref "B32") (pin "COM") (pinfunction "A_COM") (pintype "bidirectional"))
      (node (ref "B32ALT") (pin "COM") (pinfunction "A_COM") (pintype "bidirectional"))
      (node (ref "B3ALT") (pin "COM") (pinfunction "A_COM") (pintype "bidirectional"))
      (node (ref "B4") (pin "COM") (pinfunction "A_COM") (pintype "bidirectional"))
      (node (ref "B4ALT") (pin "COM") (pinfunction "A_COM") (pintype "bidirectional"))
      (node (ref "B5") (pin "COM") (pinfunction "A_COM") (pintype "bidirectional"))
      (node (ref "B5ALT") (pin "COM") (pinfunction "A_COM") (pintype "bidirectional"))
      (node (ref "B5ALT1") (pin "COM") (pinfunction "A_COM") (pintype "bidirectional"))
      (node (ref "B6") (pin "COM") (pinfunction "A_COM") (pintype "bidirectional"))
      (node (ref "B6ALT") (pin "COM") (pinfunction "A_COM") (pintype "bidirectional"))
      (node (ref "B6ALT1") (pin "COM") (pinfunction "A_COM") (pintype "bidirectional"))
      (node (ref "B7") (pin "COM") (pinfunction "A_COM") (pintype "bidirectional"))
      (node (ref "B7ALT") (pin "COM") (pinfunction "A_COM") (pintype "bidirectional"))
      (node (ref "B7ALT1") (pin "COM") (pinfunction "A_COM") (pintype "bidirectional"))
      (node (ref "B8") (pin "COM") (pinfunction "A_COM") (pintype "bidirectional"))
      (node (ref "B8ALT") (pin "COM") (pinfunction "A_COM") (pintype "bidirectional"))
      (node (ref "B9") (pin "COM") (pinfunction "A_COM") (pintype "bidirectional"))
      (node (ref "B9ALT") (pin "COM") (pinfunction "A_COM") (pintype "bidirectional"))
      (node (ref "B9ALT2") (pin "COM") (pinfunction "A_COM") (pintype "bidirectional"))
      (node (ref "C1") (pin "2") (pinfunction "2_2") (pintype "passive"))
      (node (ref "C13") (pin "2") (pinfunction "2_2") (pintype "passive"))
      (node (ref "C14") (pin "1") (pinfunction "1_1") (pintype "passive"))
      (node (ref "C15") (pin "1") (pinfunction "1_1") (pintype "passive"))
      (node (ref "C16") (pin "1") (pinfunction "1_1") (pintype "passive"))
      (node (ref "C17") (pin "1") (pinfunction "1_1") (pintype "passive"))
      (node (ref "C18") (pin "1") (pinfunction "1_1") (pintype "passive"))
      (node (ref "C19") (pin "1") (pinfunction "1_1") (pintype "passive"))
      (node (ref "C2") (pin "1") (pinfunction "1_1") (pintype "passive"))
      (node (ref "C22") (pin "1") (pinfunction "1_1") (pintype "passive"))
      (node (ref "C3") (pin "1") (pinfunction "1_1") (pintype "passive"))
      (node (ref "C4") (pin "1") (pinfunction "1_1") (pintype "passive"))
      (node (ref "C5") (pin "1") (pinfunction "1_1") (pintype "passive"))
      (node (ref "C6") (pin "1") (pinfunction "1_1") (pintype "passive"))
      (node (ref "C7") (pin "1") (pinfunction "1_1") (pintype "passive"))
      (node (ref "C8") (pin "1") (pinfunction "1_1") (pintype "passive"))
      (node (ref "IC1") (pin "15") (pinfunction "A0_15") (pintype "input"))
      (node (ref "IC1") (pin "18") (pinfunction "~{RESET}_18") (pintype "input"))
      (node (ref "IC1") (pin "9") (pinfunction "VDD_9") (pintype "power_in"))
      (node (ref "IC2") (pin "1") (pinfunction "A0_1") (pintype "input"))
      (node (ref "IC2") (pin "24") (pinfunction "A5_24") (pintype "input"))
      (node (ref "IC2") (pin "28") (pinfunction "VDD_28") (pintype "power_in"))
      (node (ref "IC2") (pin "4") (pinfunction "A3_4") (pintype "input"))
      (node (ref "IC2") (pin "5") (pinfunction "A4_5") (pintype "input"))
      (node (ref "IC3") (pin "1") (pinfunction "A0_1") (pintype "input"))
      (node (ref "IC3") (pin "24") (pinfunction "A5_24") (pintype "input"))
      (node (ref "IC3") (pin "28") (pinfunction "VDD_28") (pintype "power_in"))
      (node (ref "IC6") (pin "2") (pinfunction "A1_2") (pintype "input"))
      (node (ref "IC6") (pin "24") (pinfunction "A5_24") (pintype "input"))
      (node (ref "IC6") (pin "28") (pinfunction "VDD_28") (pintype "power_in"))
      (node (ref "IC6") (pin "4") (pinfunction "A3_4") (pintype "input"))
      (node (ref "IC6") (pin "5") (pinfunction "A4_5") (pintype "input"))
      (node (ref "IC7") (pin "16") (pinfunction "A1_16") (pintype "input"))
      (node (ref "IC7") (pin "18") (pinfunction "~{RESET}_18") (pintype "input"))
      (node (ref "IC7") (pin "9") (pinfunction "VDD_9") (pintype "power_in"))
      (node (ref "IC8") (pin "2") (pinfunction "A1_2") (pintype "input"))
      (node (ref "IC8") (pin "24") (pinfunction "A5_24") (pintype "input"))
      (node (ref "IC8") (pin "28") (pinfunction "VDD_28") (pintype "power_in"))
      (node (ref "L1") (pin "1") (pinfunction "1_1") (pintype "passive"))
      (node (ref "PC1") (pin "+") (pinfunction "+_+") (pintype "passive"))
      (node (ref "PC2") (pin "+") (pinfunction "+_+") (pintype "passive"))
      (node (ref "POT1") (pin "1") (pinfunction "E_1") (pintype "passive"))
      (node (ref "POT1ALT") (pin "1") (pinfunction "E_1") (pintype "passive"))
      (node (ref "POT2") (pin "1") (pinfunction "E_1") (pintype "passive"))
      (node (ref "R33") (pin "2") (pinfunction "2_2") (pintype "passive"))
      (node (ref "SERIAL") (pin "2") (pinfunction "2_2") (pintype "passive"))
      (node (ref "SSW1") (pin "4") (pinfunction "VDD_4") (pintype "bidirectional"))
      (node (ref "U$17") (pin "4") (pinfunction "VCC_4") (pintype "power_in"))
      (node (ref "U$94") (pin "P$2") (pinfunction "2_P$2") (pintype "passive"))
    )
    (net (code "2") (name "A0") (class "Default")
      (node (ref "C9") (pin "1") (pinfunction "1_1") (pintype "passive"))
      (node (ref "POT1") (pin "2A") (pinfunction "S_2A") (pintype "passive"))
      (node (ref "POT1ALT") (pin "2A") (pinfunction "S_2A") (pintype "passive"))
      (node (ref "POT2") (pin "2A") (pinfunction "S_2A") (pintype "passive"))
      (node (ref "SJ1") (pin "1") (pinfunction "1_1") (pintype "passive"))
      (node (ref "U$17") (pin "10") (pinfunction "PD6(PCINT22/AIN0)_10") (pintype "bidirectional"))
    )
    (net (code "3") (name "ENC1_A") (class "Default")
      (node (ref "C10") (pin "1") (pinfunction "1_1") (pintype "passive"))
      (node (ref "SW1") (pin "B") (pinfunction "B_B") (pintype "passive"))
      (node (ref "U$17") (pin "23") (pinfunction "PC0(ADC0/PCINT8)_23") (pintype "bidirectional"))
    )
    (net (code "4") (name "ENC1_B") (class "Default")
      (node (ref "C11") (pin "1") (pinfunction "1_1") (pintype "passive"))
      (node (ref "SW1") (pin "A") (pinfunction "A_A") (pintype "passive"))
      (node (ref "U$17") (pin "24") (pinfunction "PC1(ADC1/PCINT9)_24") (pintype "bidirectional"))
    )
    (net (code "5") (name "ENC1_BTN") (class "Default")
      (node (ref "C12") (pin "1") (pinfunction "1_1") (pintype "passive"))
      (node (ref "SW1") (pin "E") (pinfunction "2_E") (pintype "passive"))
      (node (ref "U$17") (pin "25") (pinfunction "PC2(ADC2/PCINT10)_25") (pintype "bidirectional"))
    )
    (net (code "6") (name "GND") (class "Default")
      (node (ref "B1") (pin "P$4") (pinfunction "SW1_P$4") (pintype "bidirectional"))
      (node (ref "B10") (pin "P$4") (pinfunction "SW1_P$4") (pintype "bidirectional"))
      (node (ref "B10ALT") (pin "P$4") (pinfunction "SW1_P$4") (pintype "bidirectional"))
      (node (ref "B11") (pin "P$4") (pinfunction "SW1_P$4") (pintype "bidirectional"))
      (node (ref "B11ALT") (pin "P$4") (pinfunction "SW1_P$4") (pintype "bidirectional"))
      (node (ref "B12") (pin "P$4") (pinfunction "SW1_P$4") (pintype "bidirectional"))
      (node (ref "B12ALT") (pin "P$4") (pinfunction "SW1_P$4") (pintype "bidirectional"))
      (node (ref "B13") (pin "P$4") (pinfunction "SW1_P$4") (pintype "bidirectional"))
      (node (ref "B13ALT") (pin "P$4") (pinfunction "SW1_P$4") (pintype "bidirectional"))
      (node (ref "B13ALT1") (pin "P$4") (pinfunction "SW1_P$4") (pintype "bidirectional"))
      (node (ref "B14") (pin "P$4") (pinfunction "SW1_P$4") (pintype "bidirectional"))
      (node (ref "B14ALT") (pin "P$4") (pinfunction "SW1_P$4") (pintype "bidirectional"))
      (node (ref "B15") (pin "P$4") (pinfunction "SW1_P$4") (pintype "bidirectional"))
      (node (ref "B15ALT") (pin "P$4") (pinfunction "SW1_P$4") (pintype "bidirectional"))
      (node (ref "B16") (pin "P$4") (pinfunction "SW1_P$4") (pintype "bidirectional"))
      (node (ref "B16ALT") (pin "P$4") (pinfunction "SW1_P$4") (pintype "bidirectional"))
      (node (ref "B17") (pin "P$4") (pinfunction "SW1_P$4") (pintype "bidirectional"))
      (node (ref "B17ALT") (pin "P$4") (pinfunction "SW1_P$4") (pintype "bidirectional"))
      (node (ref "B18") (pin "P$4") (pinfunction "SW1_P$4") (pintype "bidirectional"))
      (node (ref "B18ALT") (pin "P$4") (pinfunction "SW1_P$4") (pintype "bidirectional"))
      (node (ref "B19") (pin "P$4") (pinfunction "SW1_P$4") (pintype "bidirectional"))
      (node (ref "B19ALT") (pin "P$4") (pinfunction "SW1_P$4") (pintype "bidirectional"))
      (node (ref "B1ALT") (pin "P$4") (pinfunction "SW1_P$4") (pintype "bidirectional"))
      (node (ref "B2") (pin "P$4") (pinfunction "SW1_P$4") (pintype "bidirectional"))
      (node (ref "B20") (pin "P$4") (pinfunction "SW1_P$4") (pintype "bidirectional"))
      (node (ref "B20ALT") (pin "P$4") (pinfunction "SW1_P$4") (pintype "bidirectional"))
      (node (ref "B21") (pin "P$4") (pinfunction "SW1_P$4") (pintype "bidirectional"))
      (node (ref "B22") (pin "P$4") (pinfunction "SW1_P$4") (pintype "bidirectional"))
      (node (ref "B23") (pin "P$4") (pinfunction "SW1_P$4") (pintype "bidirectional"))
      (node (ref "B23ALT") (pin "P$4") (pinfunction "SW1_P$4") (pintype "bidirectional"))
      (node (ref "B24") (pin "P$4") (pinfunction "SW1_P$4") (pintype "bidirectional"))
      (node (ref "B24ALT") (pin "P$4") (pinfunction "SW1_P$4") (pintype "bidirectional"))
      (node (ref "B25") (pin "P$4") (pinfunction "SW1_P$4") (pintype "bidirectional"))
      (node (ref "B25ALT") (pin "P$4") (pinfunction "SW1_P$4") (pintype "bidirectional"))
      (node (ref "B26") (pin "P$4") (pinfunction "SW1_P$4") (pintype "bidirectional"))
      (node (ref "B26ALT") (pin "P$4") (pinfunction "SW1_P$4") (pintype "bidirectional"))
      (node (ref "B27") (pin "P$4") (pinfunction "SW1_P$4") (pintype "bidirectional"))
      (node (ref "B27ALT") (pin "P$4") (pinfunction "SW1_P$4") (pintype "bidirectional"))
      (node (ref "B28") (pin "P$4") (pinfunction "SW1_P$4") (pintype "bidirectional"))
      (node (ref "B28ALT") (pin "P$4") (pinfunction "SW1_P$4") (pintype "bidirectional"))
      (node (ref "B29") (pin "P$4") (pinfunction "SW1_P$4") (pintype "bidirectional"))
      (node (ref "B29ALT") (pin "P$4") (pinfunction "SW1_P$4") (pintype "bidirectional"))
      (node (ref "B2ALT") (pin "P$4") (pinfunction "SW1_P$4") (pintype "bidirectional"))
      (node (ref "B3") (pin "P$4") (pinfunction "SW1_P$4") (pintype "bidirectional"))
      (node (ref "B30") (pin "P$4") (pinfunction "SW1_P$4") (pintype "bidirectional"))
      (node (ref "B30ALT") (pin "P$4") (pinfunction "SW1_P$4") (pintype "bidirectional"))
      (node (ref "B31") (pin "P$4") (pinfunction "SW1_P$4") (pintype "bidirectional"))
      (node (ref "B31ALT") (pin "P$4") (pinfunction "SW1_P$4") (pintype "bidirectional"))
      (node (ref "B32") (pin "P$4") (pinfunction "SW1_P$4") (pintype "bidirectional"))
      (node (ref "B32ALT") (pin "P$4") (pinfunction "SW1_P$4") (pintype "bidirectional"))
      (node (ref "B3ALT") (pin "P$4") (pinfunction "SW1_P$4") (pintype "bidirectional"))
      (node (ref "B4") (pin "P$4") (pinfunction "SW1_P$4") (pintype "bidirectional"))
      (node (ref "B4ALT") (pin "P$4") (pinfunction "SW1_P$4") (pintype "bidirectional"))
      (node (ref "B5") (pin "P$4") (pinfunction "SW1_P$4") (pintype "bidirectional"))
      (node (ref "B5ALT") (pin "P$4") (pinfunction "SW1_P$4") (pintype "bidirectional"))
      (node (ref "B5ALT1") (pin "P$4") (pinfunction "SW1_P$4") (pintype "bidirectional"))
      (node (ref "B6") (pin "P$4") (pinfunction "SW1_P$4") (pintype "bidirectional"))
      (node (ref "B6ALT") (pin "P$4") (pinfunction "SW1_P$4") (pintype "bidirectional"))
      (node (ref "B6ALT1") (pin "P$4") (pinfunction "SW1_P$4") (pintype "bidirectional"))
      (node (ref "B7") (pin "P$4") (pinfunction "SW1_P$4") (pintype "bidirectional"))
      (node (ref "B7ALT") (pin "P$4") (pinfunction "SW1_P$4") (pintype "bidirectional"))
      (node (ref "B7ALT1") (pin "P$4") (pinfunction "SW1_P$4") (pintype "bidirectional"))
      (node (ref "B8") (pin "P$4") (pinfunction "SW1_P$4") (pintype "bidirectional"))
      (node (ref "B8ALT") (pin "P$4") (pinfunction "SW1_P$4") (pintype "bidirectional"))
      (node (ref "B9") (pin "P$4") (pinfunction "SW1_P$4") (pintype "bidirectional"))
      (node (ref "B9ALT") (pin "P$4") (pinfunction "SW1_P$4") (pintype "bidirectional"))
      (node (ref "B9ALT2") (pin "P$4") (pinfunction "SW1_P$4") (pintype "bidirectional"))
      (node (ref "C1") (pin "1") (pinfunction "1_1") (pintype "passive"))
      (node (ref "C10") (pin "2") (pinfunction "2_2") (pintype "passive"))
      (node (ref "C11") (pin "2") (pinfunction "2_2") (pintype "passive"))
      (node (ref "C12") (pin "2") (pinfunction "2_2") (pintype "passive"))
      (node (ref "C13") (pin "1") (pinfunction "1_1") (pintype "passive"))
      (node (ref "C14") (pin "2") (pinfunction "2_2") (pintype "passive"))
      (node (ref "C15") (pin "2") (pinfunction "2_2") (pintype "passive"))
      (node (ref "C16") (pin "2") (pinfunction "2_2") (pintype "passive"))
      (node (ref "C17") (pin "2") (pinfunction "2_2") (pintype "passive"))
      (node (ref "C18") (pin "2") (pinfunction "2_2") (pintype "passive"))
      (node (ref "C19") (pin "2") (pinfunction "2_2") (pintype "passive"))
      (node (ref "C2") (pin "2") (pinfunction "2_2") (pintype "passive"))
      (node (ref "C20") (pin "2") (pinfunction "2_2") (pintype "passive"))
      (node (ref "C22") (pin "2") (pinfunction "2_2") (pintype "passive"))
      (node (ref "C3") (pin "2") (pinfunction "2_2") (pintype "passive"))
      (node (ref "C4") (pin "2") (pinfunction "2_2") (pintype "passive"))
      (node (ref "C5") (pin "2") (pinfunction "2_2") (pintype "passive"))
      (node (ref "C6") (pin "2") (pinfunction "2_2") (pintype "passive"))
      (node (ref "C7") (pin "2") (pinfunction "2_2") (pintype "passive"))
      (node (ref "C8") (pin "2") (pinfunction "2_2") (pintype "passive"))
      (node (ref "C9") (pin "2") (pinfunction "2_2") (pintype "passive"))
      (node (ref "IC1") (pin "10") (pinfunction "VSS_10") (pintype "power_in"))
      (node (ref "IC1") (pin "16") (pinfunction "A1_16") (pintype "input"))
      (node (ref "IC1") (pin "17") (pinfunction "A2_17") (pintype "input"))
      (node (ref "IC2") (pin "14") (pinfunction "GND_14") (pintype "power_in"))
      (node (ref "IC2") (pin "2") (pinfunction "A1_2") (pintype "input"))
      (node (ref "IC2") (pin "23") (pinfunction "OE_23") (pintype "input"))
      (node (ref "IC2") (pin "25") (pinfunction "EXTCLK_25") (pintype "input"))
      (node (ref "IC2") (pin "3") (pinfunction "A2_3") (pintype "input"))
      (node (ref "IC3") (pin "14") (pinfunction "GND_14") (pintype "power_in"))
      (node (ref "IC3") (pin "2") (pinfunction "A1_2") (pintype "input"))
      (node (ref "IC3") (pin "23") (pinfunction "OE_23") (pintype "input"))
      (node (ref "IC3") (pin "25") (pinfunction "EXTCLK_25") (pintype "input"))
      (node (ref "IC3") (pin "3") (pinfunction "A2_3") (pintype "input"))
      (node (ref "IC3") (pin "4") (pinfunction "A3_4") (pintype "input"))
      (node (ref "IC3") (pin "5") (pinfunction "A4_5") (pintype "input"))
      (node (ref "IC6") (pin "1") (pinfunction "A0_1") (pintype "input"))
      (node (ref "IC6") (pin "14") (pinfunction "GND_14") (pintype "power_in"))
      (node (ref "IC6") (pin "23") (pinfunction "OE_23") (pintype "input"))
      (node (ref "IC6") (pin "25") (pinfunction "EXTCLK_25") (pintype "input"))
      (node (ref "IC6") (pin "3") (pinfunction "A2_3") (pintype "input"))
      (node (ref "IC7") (pin "10") (pinfunction "VSS_10") (pintype "power_in"))
      (node (ref "IC7") (pin "15") (pinfunction "A0_15") (pintype "input"))
      (node (ref "IC7") (pin "17") (pinfunction "A2_17") (pintype "input"))
      (node (ref "IC8") (pin "1") (pinfunction "A0_1") (pintype "input"))
      (node (ref "IC8") (pin "14") (pinfunction "GND_14") (pintype "power_in"))
      (node (ref "IC8") (pin "23") (pinfunction "OE_23") (pintype "input"))
      (node (ref "IC8") (pin "25") (pinfunction "EXTCLK_25") (pintype "input"))
      (node (ref "IC8") (pin "3") (pinfunction "A2_3") (pintype "input"))
      (node (ref "IC8") (pin "4") (pinfunction "A3_4") (pintype "input"))
      (node (ref "IC8") (pin "5") (pinfunction "A4_5") (pintype "input"))
      (node (ref "JP1") (pin "1") (pinfunction "1_1") (pintype "passive"))
      (node (ref "PC1") (pin "-") (pinfunction "-_-") (pintype "passive"))
      (node (ref "PC2") (pin "-") (pinfunction "-_-") (pintype "passive"))
      (node (ref "POT1") (pin "3") (pinfunction "A_3") (pintype "passive"))
      (node (ref "POT1ALT") (pin "3") (pinfunction "A_3") (pintype "passive"))
      (node (ref "POT2") (pin "3") (pinfunction "A_3") (pintype "passive"))
      (node (ref "SERIAL") (pin "1") (pinfunction "1_1") (pintype "passive"))
      (node (ref "SSW1") (pin "1") (pinfunction "SW1_1") (pintype "bidirectional"))
      (node (ref "SSW1") (pin "3") (pinfunction "GND_3") (pintype "bidirectional"))
      (node (ref "SW1") (pin "C") (pinfunction "C_C") (pintype "passive"))
      (node (ref "SW1") (pin "D") (pinfunction "1_D") (pintype "passive"))
      (node (ref "U$17") (pin "21") (pinfunction "GND2_21") (pintype "power_in"))
      (node (ref "U$17") (pin "30") (pinfunction "PD0(PCINT16)_30") (pintype "bidirectional"))
      (node (ref "U$17") (pin "31") (pinfunction "PD1(PCINT17)_31") (pintype "bidirectional"))
      (node (ref "U$17") (pin "32") (pinfunction "PD2(INT0/PCINT18)_32") (pintype "bidirectional"))
      (node (ref "U$17") (pin "5") (pinfunction "GND1_5") (pintype "power_in"))
      (node (ref "U$25") (pin "P$1") (pinfunction "1_P$1") (pintype "passive"))
      (node (ref "U$26") (pin "P$1") (pinfunction "1_P$1") (pintype "passive"))
      (node (ref "U$27") (pin "P$1") (pinfunction "1_P$1") (pintype "passive"))
      (node (ref "U$28") (pin "P$1") (pinfunction "1_P$1") (pintype "passive"))
      (node (ref "U$51") (pin "P$1") (pinfunction "1_P$1") (pintype "passive"))
      (node (ref "U$94") (pin "P$1") (pinfunction "1_P$1") (pintype "passive"))
    )
    (net (code "7") (name "GPA0") (class "Default")
      (node (ref "B8") (pin "P$5") (pinfunction "SW2_P$5") (pintype "bidirectional"))
      (node (ref "B8ALT") (pin "P$5") (pinfunction "SW2_P$5") (pintype "bidirectional"))
      (node (ref "IC1") (pin "21") (pinfunction "GPA0_21") (pintype "bidirectional"))
    )
    (net (code "8") (name "GPA1") (class "Default")
      (node (ref "B7") (pin "P$5") (pinfunction "SW2_P$5") (pintype "bidirectional"))
      (node (ref "B7ALT") (pin "P$5") (pinfunction "SW2_P$5") (pintype "bidirectional"))
      (node (ref "B7ALT1") (pin "P$5") (pinfunction "SW2_P$5") (pintype "bidirectional"))
      (node (ref "IC1") (pin "22") (pinfunction "GPA1_22") (pintype "bidirectional"))
    )
    (net (code "9") (name "GPA2") (class "Default")
      (node (ref "B6") (pin "P$5") (pinfunction "SW2_P$5") (pintype "bidirectional"))
      (node (ref "B6ALT") (pin "P$5") (pinfunction "SW2_P$5") (pintype "bidirectional"))
      (node (ref "B6ALT1") (pin "P$5") (pinfunction "SW2_P$5") (pintype "bidirectional"))
      (node (ref "IC1") (pin "23") (pinfunction "GPA2_23") (pintype "bidirectional"))
    )
    (net (code "10") (name "GPA3") (class "Default")
      (node (ref "B5") (pin "P$5") (pinfunction "SW2_P$5") (pintype "bidirectional"))
      (node (ref "B5ALT") (pin "P$5") (pinfunction "SW2_P$5") (pintype "bidirectional"))
      (node (ref "B5ALT1") (pin "P$5") (pinfunction "SW2_P$5") (pintype "bidirectional"))
      (node (ref "IC1") (pin "24") (pinfunction "GPA3_24") (pintype "bidirectional"))
    )
    (net (code "11") (name "GPA4") (class "Default")
      (node (ref "B1") (pin "P$5") (pinfunction "SW2_P$5") (pintype "bidirectional"))
      (node (ref "B1ALT") (pin "P$5") (pinfunction "SW2_P$5") (pintype "bidirectional"))
      (node (ref "IC1") (pin "25") (pinfunction "GPA4_25") (pintype "bidirectional"))
    )
    (net (code "12") (name "GPA4S") (class "Default")
      (node (ref "SSW1") (pin "2") (pinfunction "SW2_2") (pintype "bidirectional"))
      (node (ref "U$17") (pin "22") (pinfunction "PA1(ADC7/PCINT25)_22") (pintype "bidirectional"))
    )
    (net (code "13") (name "GPA5") (class "Default")
      (node (ref "B2") (pin "P$5") (pinfunction "SW2_P$5") (pintype "bidirectional"))
      (node (ref "B2ALT") (pin "P$5") (pinfunction "SW2_P$5") (pintype "bidirectional"))
      (node (ref "IC1") (pin "26") (pinfunction "GPA5_26") (pintype "bidirectional"))
    )
    (net (code "14") (name "GPA6") (class "Default")
      (node (ref "B3") (pin "P$5") (pinfunction "SW2_P$5") (pintype "bidirectional"))
      (node (ref "B3ALT") (pin "P$5") (pinfunction "SW2_P$5") (pintype "bidirectional"))
      (node (ref "IC1") (pin "27") (pinfunction "GPA6_27") (pintype "bidirectional"))
    )
    (net (code "15") (name "GPA7") (class "Default")
      (node (ref "B4") (pin "P$5") (pinfunction "SW2_P$5") (pintype "bidirectional"))
      (node (ref "B4ALT") (pin "P$5") (pinfunction "SW2_P$5") (pintype "bidirectional"))
      (node (ref "IC1") (pin "28") (pinfunction "GPA7_28") (pintype "bidirectional"))
    )
    (net (code "16") (name "GPA8") (class "Default")
      (node (ref "B16") (pin "P$5") (pinfunction "SW2_P$5") (pintype "bidirectional"))
      (node (ref "B16ALT") (pin "P$5") (pinfunction "SW2_P$5") (pintype "bidirectional"))
      (node (ref "IC1") (pin "1") (pinfunction "GPB0_1") (pintype "bidirectional"))
    )
    (net (code "17") (name "GPA9") (class "Default")
      (node (ref "B15") (pin "P$5") (pinfunction "SW2_P$5") (pintype "bidirectional"))
      (node (ref "B15ALT") (pin "P$5") (pinfunction "SW2_P$5") (pintype "bidirectional"))
      (node (ref "IC1") (pin "2") (pinfunction "GPB1_2") (pintype "bidirectional"))
    )
    (net (code "18") (name "GPA10") (class "Default")
      (node (ref "B14") (pin "P$5") (pinfunction "SW2_P$5") (pintype "bidirectional"))
      (node (ref "B14ALT") (pin "P$5") (pinfunction "SW2_P$5") (pintype "bidirectional"))
      (node (ref "IC1") (pin "3") (pinfunction "GPB2_3") (pintype "bidirectional"))
    )
    (net (code "19") (name "GPA11") (class "Default")
      (node (ref "B13") (pin "P$5") (pinfunction "SW2_P$5") (pintype "bidirectional"))
      (node (ref "B13ALT") (pin "P$5") (pinfunction "SW2_P$5") (pintype "bidirectional"))
      (node (ref "B13ALT1") (pin "P$5") (pinfunction "SW2_P$5") (pintype "bidirectional"))
      (node (ref "IC1") (pin "4") (pinfunction "GPB3_4") (pintype "bidirectional"))
    )
    (net (code "20") (name "GPA12") (class "Default")
      (node (ref "B9") (pin "P$5") (pinfunction "SW2_P$5") (pintype "bidirectional"))
      (node (ref "B9ALT") (pin "P$5") (pinfunction "SW2_P$5") (pintype "bidirectional"))
      (node (ref "B9ALT2") (pin "P$5") (pinfunction "SW2_P$5") (pintype "bidirectional"))
      (node (ref "IC1") (pin "5") (pinfunction "GPB4_5") (pintype "bidirectional"))
    )
    (net (code "21") (name "GPA13") (class "Default")
      (node (ref "B10") (pin "P$5") (pinfunction "SW2_P$5") (pintype "bidirectional"))
      (node (ref "B10ALT") (pin "P$5") (pinfunction "SW2_P$5") (pintype "bidirectional"))
      (node (ref "IC1") (pin "6") (pinfunction "GPB5_6") (pintype "bidirectional"))
    )
    (net (code "22") (name "GPA14") (class "Default")
      (node (ref "B11") (pin "P$5") (pinfunction "SW2_P$5") (pintype "bidirectional"))
      (node (ref "B11ALT") (pin "P$5") (pinfunction "SW2_P$5") (pintype "bidirectional"))
      (node (ref "IC1") (pin "7") (pinfunction "GPB6_7") (pintype "bidirectional"))
    )
    (net (code "23") (name "GPA15") (class "Default")
      (node (ref "B12") (pin "P$5") (pinfunction "SW2_P$5") (pintype "bidirectional"))
      (node (ref "B12ALT") (pin "P$5") (pinfunction "SW2_P$5") (pintype "bidirectional"))
      (node (ref "IC1") (pin "8") (pinfunction "GPB7_8") (pintype "bidirectional"))
    )
    (net (code "24") (name "GPA16") (class "Default")
      (node (ref "B24") (pin "P$5") (pinfunction "SW2_P$5") (pintype "bidirectional"))
      (node (ref "B24ALT") (pin "P$5") (pinfunction "SW2_P$5") (pintype "bidirectional"))
      (node (ref "IC7") (pin "21") (pinfunction "GPA0_21") (pintype "bidirectional"))
    )
    (net (code "25") (name "GPA17") (class "Default")
      (node (ref "B23") (pin "P$5") (pinfunction "SW2_P$5") (pintype "bidirectional"))
      (node (ref "B23ALT") (pin "P$5") (pinfunction "SW2_P$5") (pintype "bidirectional"))
      (node (ref "IC7") (pin "22") (pinfunction "GPA1_22") (pintype "bidirectional"))
    )
    (net (code "26") (name "GPA18") (class "Default")
      (node (ref "B22") (pin "P$5") (pinfunction "SW2_P$5") (pintype "bidirectional"))
      (node (ref "IC7") (pin "23") (pinfunction "GPA2_23") (pintype "bidirectional"))
    )
    (net (code "27") (name "GPA19") (class "Default")
      (node (ref "B21") (pin "P$5") (pinfunction "SW2_P$5") (pintype "bidirectional"))
      (node (ref "IC7") (pin "24") (pinfunction "GPA3_24") (pintype "bidirectional"))
    )
    (net (code "28") (name "GPA20") (class "Default")
      (node (ref "B17") (pin "P$5") (pinfunction "SW2_P$5") (pintype "bidirectional"))
      (node (ref "B17ALT") (pin "P$5") (pinfunction "SW2_P$5") (pintype "bidirectional"))
      (node (ref "IC7") (pin "25") (pinfunction "GPA4_25") (pintype "bidirectional"))
    )
    (net (code "29") (name "GPA21") (class "Default")
      (node (ref "B18") (pin "P$5") (pinfunction "SW2_P$5") (pintype "bidirectional"))
      (node (ref "B18ALT") (pin "P$5") (pinfunction "SW2_P$5") (pintype "bidirectional"))
      (node (ref "IC7") (pin "26") (pinfunction "GPA5_26") (pintype "bidirectional"))
    )
    (net (code "30") (name "GPA22") (class "Default")
      (node (ref "B19") (pin "P$5") (pinfunction "SW2_P$5") (pintype "bidirectional"))
      (node (ref "B19ALT") (pin "P$5") (pinfunction "SW2_P$5") (pintype "bidirectional"))
      (node (ref "IC7") (pin "27") (pinfunction "GPA6_27") (pintype "bidirectional"))
    )
    (net (code "31") (name "GPA23") (class "Default")
      (node (ref "B20") (pin "P$5") (pinfunction "SW2_P$5") (pintype "bidirectional"))
      (node (ref "B20ALT") (pin "P$5") (pinfunction "SW2_P$5") (pintype "bidirectional"))
      (node (ref "IC7") (pin "28") (pinfunction "GPA7_28") (pintype "bidirectional"))
    )
    (net (code "32") (name "GPA24") (class "Default")
      (node (ref "B32") (pin "P$5") (pinfunction "SW2_P$5") (pintype "bidirectional"))
      (node (ref "B32ALT") (pin "P$5") (pinfunction "SW2_P$5") (pintype "bidirectional"))
      (node (ref "IC7") (pin "1") (pinfunction "GPB0_1") (pintype "bidirectional"))
    )
    (net (code "33") (name "GPA25") (class "Default")
      (node (ref "B31") (pin "P$5") (pinfunction "SW2_P$5") (pintype "bidirectional"))
      (node (ref "B31ALT") (pin "P$5") (pinfunction "SW2_P$5") (pintype "bidirectional"))
      (node (ref "IC7") (pin "2") (pinfunction "GPB1_2") (pintype "bidirectional"))
    )
    (net (code "34") (name "GPA26") (class "Default")
      (node (ref "B30") (pin "P$5") (pinfunction "SW2_P$5") (pintype "bidirectional"))
      (node (ref "B30ALT") (pin "P$5") (pinfunction "SW2_P$5") (pintype "bidirectional"))
      (node (ref "IC7") (pin "3") (pinfunction "GPB2_3") (pintype "bidirectional"))
    )
    (net (code "35") (name "GPA27") (class "Default")
      (node (ref "B29") (pin "P$5") (pinfunction "SW2_P$5") (pintype "bidirectional"))
      (node (ref "B29ALT") (pin "P$5") (pinfunction "SW2_P$5") (pintype "bidirectional"))
      (node (ref "IC7") (pin "4") (pinfunction "GPB3_4") (pintype "bidirectional"))
    )
    (net (code "36") (name "GPA28") (class "Default")
      (node (ref "B25") (pin "P$5") (pinfunction "SW2_P$5") (pintype "bidirectional"))
      (node (ref "B25ALT") (pin "P$5") (pinfunction "SW2_P$5") (pintype "bidirectional"))
      (node (ref "IC7") (pin "5") (pinfunction "GPB4_5") (pintype "bidirectional"))
    )
    (net (code "37") (name "GPA29") (class "Default")
      (node (ref "B26") (pin "P$5") (pinfunction "SW2_P$5") (pintype "bidirectional"))
      (node (ref "B26ALT") (pin "P$5") (pinfunction "SW2_P$5") (pintype "bidirectional"))
      (node (ref "IC7") (pin "6") (pinfunction "GPB5_6") (pintype "bidirectional"))
    )
    (net (code "38") (name "GPA30") (class "Default")
      (node (ref "B27") (pin "P$5") (pinfunction "SW2_P$5") (pintype "bidirectional"))
      (node (ref "B27ALT") (pin "P$5") (pinfunction "SW2_P$5") (pintype "bidirectional"))
      (node (ref "IC7") (pin "7") (pinfunction "GPB6_7") (pintype "bidirectional"))
    )
    (net (code "39") (name "GPA31") (class "Default")
      (node (ref "B28") (pin "P$5") (pinfunction "SW2_P$5") (pintype "bidirectional"))
      (node (ref "B28ALT") (pin "P$5") (pinfunction "SW2_P$5") (pintype "bidirectional"))
      (node (ref "IC7") (pin "8") (pinfunction "GPB7_8") (pintype "bidirectional"))
    )
    (net (code "40") (name "GPB4") (class "Default")
      (node (ref "SSW1") (pin "8") (pinfunction "SS_8") (pintype "bidirectional"))
      (node (ref "U$17") (pin "19") (pinfunction "PA0(ADC6/PCINT24)_19") (pintype "bidirectional"))
    )
    (net (code "41") (name "I2C_SCL") (class "Default")
      (node (ref "IC1") (pin "12") (pinfunction "SCL_12") (pintype "input"))
      (node (ref "IC2") (pin "26") (pinfunction "SCL_26") (pintype "input"))
      (node (ref "IC3") (pin "26") (pinfunction "SCL_26") (pintype "input"))
      (node (ref "IC6") (pin "26") (pinfunction "SCL_26") (pintype "input"))
      (node (ref "IC7") (pin "12") (pinfunction "SCL_12") (pintype "input"))
      (node (ref "IC8") (pin "26") (pinfunction "SCL_26") (pintype "input"))
      (node (ref "SERIAL") (pin "4") (pinfunction "4_4") (pintype "passive"))
      (node (ref "U$17") (pin "28") (pinfunction "PC5(ADC5/SCL/PCINT13)_28") (pintype "bidirectional"))
      (node (ref "U$94") (pin "P$4") (pinfunction "4_P$4") (pintype "passive"))
    )
    (net (code "42") (name "I2C_SDA") (class "Default")
      (node (ref "IC1") (pin "13") (pinfunction "SDA_13") (pintype "bidirectional"))
      (node (ref "IC2") (pin "27") (pinfunction "SDA_27") (pintype "input"))
      (node (ref "IC3") (pin "27") (pinfunction "SDA_27") (pintype "input"))
      (node (ref "IC6") (pin "27") (pinfunction "SDA_27") (pintype "input"))
      (node (ref "IC7") (pin "13") (pinfunction "SDA_13") (pintype "bidirectional"))
      (node (ref "IC8") (pin "27") (pinfunction "SDA_27") (pintype "input"))
      (node (ref "SERIAL") (pin "3") (pinfunction "3_3") (pintype "passive"))
      (node (ref "U$17") (pin "27") (pinfunction "PC4(ADC4/SDA/PCINT12)_27") (pintype "bidirectional"))
      (node (ref "U$94") (pin "P$3") (pinfunction "3_P$3") (pintype "passive"))
    )
    (net (code "43") (name "L0") (class "Default")
      (node (ref "B1") (pin "P$2") (pinfunction "K1_P$2") (pintype "bidirectional"))
      (node (ref "B1ALT") (pin "P$2") (pinfunction "K1_P$2") (pintype "bidirectional"))
      (node (ref "R20") (pin "1") (pinfunction "1_1") (pintype "passive"))
    )
    (net (code "44") (name "L1") (class "Default")
      (node (ref "B1") (pin "P$3") (pinfunction "K2_P$3") (pintype "bidirectional"))
      (node (ref "B1ALT") (pin "P$3") (pinfunction "K2_P$3") (pintype "bidirectional"))
      (node (ref "R19") (pin "1") (pinfunction "1_1") (pintype "passive"))
    )
    (net (code "45") (name "L2") (class "Default")
      (node (ref "B2") (pin "P$2") (pinfunction "K1_P$2") (pintype "bidirectional"))
      (node (ref "B2ALT") (pin "P$2") (pinfunction "K1_P$2") (pintype "bidirectional"))
      (node (ref "R18") (pin "1") (pinfunction "1_1") (pintype "passive"))
    )
    (net (code "46") (name "L3") (class "Default")
      (node (ref "B2") (pin "P$3") (pinfunction "K2_P$3") (pintype "bidirectional"))
      (node (ref "B2ALT") (pin "P$3") (pinfunction "K2_P$3") (pintype "bidirectional"))
      (node (ref "R17") (pin "1") (pinfunction "1_1") (pintype "passive"))
    )
    (net (code "47") (name "L4") (class "Default")
      (node (ref "B3") (pin "P$2") (pinfunction "K1_P$2") (pintype "bidirectional"))
      (node (ref "B3ALT") (pin "P$2") (pinfunction "K1_P$2") (pintype "bidirectional"))
      (node (ref "R16") (pin "1") (pinfunction "1_1") (pintype "passive"))
    )
    (net (code "48") (name "L5") (class "Default")
      (node (ref "B3") (pin "P$3") (pinfunction "K2_P$3") (pintype "bidirectional"))
      (node (ref "B3ALT") (pin "P$3") (pinfunction "K2_P$3") (pintype "bidirectional"))
      (node (ref "R15") (pin "1") (pinfunction "1_1") (pintype "passive"))
    )
    (net (code "49") (name "L6") (class "Default")
      (node (ref "B4") (pin "P$2") (pinfunction "K1_P$2") (pintype "bidirectional"))
      (node (ref "B4ALT") (pin "P$2") (pinfunction "K1_P$2") (pintype "bidirectional"))
      (node (ref "R14") (pin "1") (pinfunction "1_1") (pintype "passive"))
    )
    (net (code "50") (name "L7") (class "Default")
      (node (ref "B4") (pin "P$3") (pinfunction "K2_P$3") (pintype "bidirectional"))
      (node (ref "B4ALT") (pin "P$3") (pinfunction "K2_P$3") (pintype "bidirectional"))
      (node (ref "R13") (pin "1") (pinfunction "1_1") (pintype "passive"))
    )
    (net (code "51") (name "L8") (class "Default")
      (node (ref "B5") (pin "P$2") (pinfunction "K1_P$2") (pintype "bidirectional"))
      (node (ref "B5ALT") (pin "P$2") (pinfunction "K1_P$2") (pintype "bidirectional"))
      (node (ref "B5ALT1") (pin "P$2") (pinfunction "K1_P$2") (pintype "bidirectional"))
      (node (ref "R12") (pin "1") (pinfunction "1_1") (pintype "passive"))
    )
    (net (code "52") (name "L9") (class "Default")
      (node (ref "B5") (pin "P$3") (pinfunction "K2_P$3") (pintype "bidirectional"))
      (node (ref "B5ALT") (pin "P$3") (pinfunction "K2_P$3") (pintype "bidirectional"))
      (node (ref "B5ALT1") (pin "P$3") (pinfunction "K2_P$3") (pintype "bidirectional"))
      (node (ref "R11") (pin "1") (pinfunction "1_1") (pintype "passive"))
    )
    (net (code "53") (name "L10") (class "Default")
      (node (ref "B6") (pin "P$2") (pinfunction "K1_P$2") (pintype "bidirectional"))
      (node (ref "B6ALT") (pin "P$2") (pinfunction "K1_P$2") (pintype "bidirectional"))
      (node (ref "B6ALT1") (pin "P$2") (pinfunction "K1_P$2") (pintype "bidirectional"))
      (node (ref "R10") (pin "1") (pinfunction "1_1") (pintype "passive"))
    )
    (net (code "54") (name "L11") (class "Default")
      (node (ref "B6") (pin "P$3") (pinfunction "K2_P$3") (pintype "bidirectional"))
      (node (ref "B6ALT") (pin "P$3") (pinfunction "K2_P$3") (pintype "bidirectional"))
      (node (ref "B6ALT1") (pin "P$3") (pinfunction "K2_P$3") (pintype "bidirectional"))
      (node (ref "R9") (pin "1") (pinfunction "1_1") (pintype "passive"))
    )
    (net (code "55") (name "L12") (class "Default")
      (node (ref "B7") (pin "P$2") (pinfunction "K1_P$2") (pintype "bidirectional"))
      (node (ref "B7ALT") (pin "P$2") (pinfunction "K1_P$2") (pintype "bidirectional"))
      (node (ref "B7ALT1") (pin "P$2") (pinfunction "K1_P$2") (pintype "bidirectional"))
      (node (ref "R8") (pin "1") (pinfunction "1_1") (pintype "passive"))
    )
    (net (code "56") (name "L13") (class "Default")
      (node (ref "B7") (pin "P$3") (pinfunction "K2_P$3") (pintype "bidirectional"))
      (node (ref "B7ALT") (pin "P$3") (pinfunction "K2_P$3") (pintype "bidirectional"))
      (node (ref "B7ALT1") (pin "P$3") (pinfunction "K2_P$3") (pintype "bidirectional"))
      (node (ref "R7") (pin "1") (pinfunction "1_1") (pintype "passive"))
    )
    (net (code "57") (name "L14") (class "Default")
      (node (ref "B8") (pin "P$2") (pinfunction "K1_P$2") (pintype "bidirectional"))
      (node (ref "B8ALT") (pin "P$2") (pinfunction "K1_P$2") (pintype "bidirectional"))
      (node (ref "R6") (pin "1") (pinfunction "1_1") (pintype "passive"))
    )
    (net (code "58") (name "L15") (class "Default")
      (node (ref "B8") (pin "P$3") (pinfunction "K2_P$3") (pintype "bidirectional"))
      (node (ref "B8ALT") (pin "P$3") (pinfunction "K2_P$3") (pintype "bidirectional"))
      (node (ref "R5") (pin "1") (pinfunction "1_1") (pintype "passive"))
    )
    (net (code "59") (name "L16") (class "Default")
      (node (ref "B9") (pin "P$2") (pinfunction "K1_P$2") (pintype "bidirectional"))
      (node (ref "B9ALT") (pin "P$2") (pinfunction "K1_P$2") (pintype "bidirectional"))
      (node (ref "B9ALT2") (pin "P$2") (pinfunction "K1_P$2") (pintype "bidirectional"))
      (node (ref "R32") (pin "1") (pinfunction "1_1") (pintype "passive"))
    )
    (net (code "60") (name "L17") (class "Default")
      (node (ref "B9") (pin "P$3") (pinfunction "K2_P$3") (pintype "bidirectional"))
      (node (ref "B9ALT") (pin "P$3") (pinfunction "K2_P$3") (pintype "bidirectional"))
      (node (ref "B9ALT2") (pin "P$3") (pinfunction "K2_P$3") (pintype "bidirectional"))
      (node (ref "R31") (pin "1") (pinfunction "1_1") (pintype "passive"))
    )
    (net (code "61") (name "L18") (class "Default")
      (node (ref "B10") (pin "P$2") (pinfunction "K1_P$2") (pintype "bidirectional"))
      (node (ref "B10ALT") (pin "P$2") (pinfunction "K1_P$2") (pintype "bidirectional"))
      (node (ref "R30") (pin "1") (pinfunction "1_1") (pintype "passive"))
    )
    (net (code "62") (name "L19") (class "Default")
      (node (ref "B10") (pin "P$3") (pinfunction "K2_P$3") (pintype "bidirectional"))
      (node (ref "B10ALT") (pin "P$3") (pinfunction "K2_P$3") (pintype "bidirectional"))
      (node (ref "R29") (pin "1") (pinfunction "1_1") (pintype "passive"))
    )
    (net (code "63") (name "L20") (class "Default")
      (node (ref "B11") (pin "P$2") (pinfunction "K1_P$2") (pintype "bidirectional"))
      (node (ref "B11ALT") (pin "P$2") (pinfunction "K1_P$2") (pintype "bidirectional"))
      (node (ref "R28") (pin "1") (pinfunction "1_1") (pintype "passive"))
    )
    (net (code "64") (name "L21") (class "Default")
      (node (ref "B11") (pin "P$3") (pinfunction "K2_P$3") (pintype "bidirectional"))
      (node (ref "B11ALT") (pin "P$3") (pinfunction "K2_P$3") (pintype "bidirectional"))
      (node (ref "R27") (pin "1") (pinfunction "1_1") (pintype "passive"))
    )
    (net (code "65") (name "L22") (class "Default")
      (node (ref "B12") (pin "P$2") (pinfunction "K1_P$2") (pintype "bidirectional"))
      (node (ref "B12ALT") (pin "P$2") (pinfunction "K1_P$2") (pintype "bidirectional"))
      (node (ref "R57") (pin "1") (pinfunction "1_1") (pintype "passive"))
    )
    (net (code "66") (name "L23") (class "Default")
      (node (ref "B12") (pin "P$3") (pinfunction "K2_P$3") (pintype "bidirectional"))
      (node (ref "B12ALT") (pin "P$3") (pinfunction "K2_P$3") (pintype "bidirectional"))
      (node (ref "R56") (pin "1") (pinfunction "1_1") (pintype "passive"))
    )
    (net (code "67") (name "L24") (class "Default")
      (node (ref "B13") (pin "P$2") (pinfunction "K1_P$2") (pintype "bidirectional"))
      (node (ref "B13ALT") (pin "P$2") (pinfunction "K1_P$2") (pintype "bidirectional"))
      (node (ref "B13ALT1") (pin "P$2") (pinfunction "K1_P$2") (pintype "bidirectional"))
      (node (ref "R63") (pin "1") (pinfunction "1_1") (pintype "passive"))
    )
    (net (code "68") (name "L25") (class "Default")
      (node (ref "B13") (pin "P$3") (pinfunction "K2_P$3") (pintype "bidirectional"))
      (node (ref "B13ALT") (pin "P$3") (pinfunction "K2_P$3") (pintype "bidirectional"))
      (node (ref "B13ALT1") (pin "P$3") (pinfunction "K2_P$3") (pintype "bidirectional"))
      (node (ref "R62") (pin "1") (pinfunction "1_1") (pintype "passive"))
    )
    (net (code "69") (name "L26") (class "Default")
      (node (ref "B14") (pin "P$2") (pinfunction "K1_P$2") (pintype "bidirectional"))
      (node (ref "B14ALT") (pin "P$2") (pinfunction "K1_P$2") (pintype "bidirectional"))
      (node (ref "R61") (pin "1") (pinfunction "1_1") (pintype "passive"))
    )
    (net (code "70") (name "L27") (class "Default")
      (node (ref "B14") (pin "P$3") (pinfunction "K2_P$3") (pintype "bidirectional"))
      (node (ref "B14ALT") (pin "P$3") (pinfunction "K2_P$3") (pintype "bidirectional"))
      (node (ref "R60") (pin "1") (pinfunction "1_1") (pintype "passive"))
    )
    (net (code "71") (name "L28") (class "Default")
      (node (ref "B15") (pin "P$2") (pinfunction "K1_P$2") (pintype "bidirectional"))
      (node (ref "B15ALT") (pin "P$2") (pinfunction "K1_P$2") (pintype "bidirectional"))
      (node (ref "R59") (pin "1") (pinfunction "1_1") (pintype "passive"))
    )
    (net (code "72") (name "L29") (class "Default")
      (node (ref "B15") (pin "P$3") (pinfunction "K2_P$3") (pintype "bidirectional"))
      (node (ref "B15ALT") (pin "P$3") (pinfunction "K2_P$3") (pintype "bidirectional"))
      (node (ref "R58") (pin "1") (pinfunction "1_1") (pintype "passive"))
    )
    (net (code "73") (name "L30") (class "Default")
      (node (ref "B16") (pin "P$2") (pinfunction "K1_P$2") (pintype "bidirectional"))
      (node (ref "B16ALT") (pin "P$2") (pinfunction "K1_P$2") (pintype "bidirectional"))
      (node (ref "R65") (pin "1") (pinfunction "1_1") (pintype "passive"))
    )
    (net (code "74") (name "L31") (class "Default")
      (node (ref "B16") (pin "P$3") (pinfunction "K2_P$3") (pintype "bidirectional"))
      (node (ref "B16ALT") (pin "P$3") (pinfunction "K2_P$3") (pintype "bidirectional"))
      (node (ref "R64") (pin "1") (pinfunction "1_1") (pintype "passive"))
    )
    (net (code "75") (name "L32") (class "Default")
      (node (ref "B17") (pin "P$2") (pinfunction "K1_P$2") (pintype "bidirectional"))
      (node (ref "B17ALT") (pin "P$2") (pinfunction "K1_P$2") (pintype "bidirectional"))
      (node (ref "R39") (pin "1") (pinfunction "1_1") (pintype "passive"))
    )
    (net (code "76") (name "L33") (class "Default")
      (node (ref "B17") (pin "P$3") (pinfunction "K2_P$3") (pintype "bidirectional"))
      (node (ref "B17ALT") (pin "P$3") (pinfunction "K2_P$3") (pintype "bidirectional"))
      (node (ref "R38") (pin "1") (pinfunction "1_1") (pintype "passive"))
    )
    (net (code "77") (name "L34") (class "Default")
      (node (ref "B18") (pin "P$2") (pinfunction "K1_P$2") (pintype "bidirectional"))
      (node (ref "B18ALT") (pin "P$2") (pinfunction "K1_P$2") (pintype "bidirectional"))
      (node (ref "R37") (pin "1") (pinfunction "1_1") (pintype "passive"))
    )
    (net (code "78") (name "L35") (class "Default")
      (node (ref "B18") (pin "P$3") (pinfunction "K2_P$3") (pintype "bidirectional"))
      (node (ref "B18ALT") (pin "P$3") (pinfunction "K2_P$3") (pintype "bidirectional"))
      (node (ref "R36") (pin "1") (pinfunction "1_1") (pintype "passive"))
    )
    (net (code "79") (name "L36") (class "Default")
      (node (ref "B19") (pin "P$2") (pinfunction "K1_P$2") (pintype "bidirectional"))
      (node (ref "B19ALT") (pin "P$2") (pinfunction "K1_P$2") (pintype "bidirectional"))
      (node (ref "R35") (pin "1") (pinfunction "1_1") (pintype "passive"))
    )
    (net (code "80") (name "L37") (class "Default")
      (node (ref "B19") (pin "P$3") (pinfunction "K2_P$3") (pintype "bidirectional"))
      (node (ref "B19ALT") (pin "P$3") (pinfunction "K2_P$3") (pintype "bidirectional"))
      (node (ref "R34") (pin "1") (pinfunction "1_1") (pintype "passive"))
    )
    (net (code "81") (name "L38") (class "Default")
      (node (ref "B20") (pin "P$2") (pinfunction "K1_P$2") (pintype "bidirectional"))
      (node (ref "B20ALT") (pin "P$2") (pinfunction "K1_P$2") (pintype "bidirectional"))
      (node (ref "R26") (pin "1") (pinfunction "1_1") (pintype "passive"))
    )
    (net (code "82") (name "L39") (class "Default")
      (node (ref "B20") (pin "P$3") (pinfunction "K2_P$3") (pintype "bidirectional"))
      (node (ref "B20ALT") (pin "P$3") (pinfunction "K2_P$3") (pintype "bidirectional"))
      (node (ref "R25") (pin "1") (pinfunction "1_1") (pintype "passive"))
    )
    (net (code "83") (name "L40") (class "Default")
      (node (ref "B21") (pin "P$2") (pinfunction "K1_P$2") (pintype "bidirectional"))
      (node (ref "R24") (pin "1") (pinfunction "1_1") (pintype "passive"))
    )
    (net (code "84") (name "L41") (class "Default")
      (node (ref "B21") (pin "P$3") (pinfunction "K2_P$3") (pintype "bidirectional"))
      (node (ref "R23") (pin "1") (pinfunction "1_1") (pintype "passive"))
    )
    (net (code "85") (name "L42") (class "Default")
      (node (ref "B22") (pin "P$2") (pinfunction "K1_P$2") (pintype "bidirectional"))
      (node (ref "R22") (pin "1") (pinfunction "1_1") (pintype "passive"))
    )
    (net (code "86") (name "L43") (class "Default")
      (node (ref "B22") (pin "P$3") (pinfunction "K2_P$3") (pintype "bidirectional"))
      (node (ref "R21") (pin "1") (pinfunction "1_1") (pintype "passive"))
    )
    (net (code "87") (name "L44") (class "Default")
      (node (ref "B23") (pin "P$2") (pinfunction "K1_P$2") (pintype "bidirectional"))
      (node (ref "B23ALT") (pin "P$2") (pinfunction "K1_P$2") (pintype "bidirectional"))
      (node (ref "R4") (pin "1") (pinfunction "1_1") (pintype "passive"))
    )
    (net (code "88") (name "L45") (class "Default")
      (node (ref "B23") (pin "P$3") (pinfunction "K2_P$3") (pintype "bidirectional"))
      (node (ref "B23ALT") (pin "P$3") (pinfunction "K2_P$3") (pintype "bidirectional"))
      (node (ref "R3") (pin "1") (pinfunction "1_1") (pintype "passive"))
    )
    (net (code "89") (name "L46") (class "Default")
      (node (ref "B24") (pin "P$2") (pinfunction "K1_P$2") (pintype "bidirectional"))
      (node (ref "B24ALT") (pin "P$2") (pinfunction "K1_P$2") (pintype "bidirectional"))
      (node (ref "R2") (pin "1") (pinfunction "1_1") (pintype "passive"))
    )
    (net (code "90") (name "L47") (class "Default")
      (node (ref "B24") (pin "P$3") (pinfunction "K2_P$3") (pintype "bidirectional"))
      (node (ref "B24ALT") (pin "P$3") (pinfunction "K2_P$3") (pintype "bidirectional"))
      (node (ref "R1") (pin "1") (pinfunction "1_1") (pintype "passive"))
    )
    (net (code "91") (name "L48") (class "Default")
      (node (ref "B25") (pin "P$2") (pinfunction "K1_P$2") (pintype "bidirectional"))
      (node (ref "B25ALT") (pin "P$2") (pinfunction "K1_P$2") (pintype "bidirectional"))
      (node (ref "R55") (pin "1") (pinfunction "1_1") (pintype "passive"))
    )
    (net (code "92") (name "L49") (class "Default")
      (node (ref "B25") (pin "P$3") (pinfunction "K2_P$3") (pintype "bidirectional"))
      (node (ref "B25ALT") (pin "P$3") (pinfunction "K2_P$3") (pintype "bidirectional"))
      (node (ref "R54") (pin "1") (pinfunction "1_1") (pintype "passive"))
    )
    (net (code "93") (name "L50") (class "Default")
      (node (ref "B26") (pin "P$2") (pinfunction "K1_P$2") (pintype "bidirectional"))
      (node (ref "B26ALT") (pin "P$2") (pinfunction "K1_P$2") (pintype "bidirectional"))
      (node (ref "R53") (pin "1") (pinfunction "1_1") (pintype "passive"))
    )
    (net (code "94") (name "L51") (class "Default")
      (node (ref "B26") (pin "P$3") (pinfunction "K2_P$3") (pintype "bidirectional"))
      (node (ref "B26ALT") (pin "P$3") (pinfunction "K2_P$3") (pintype "bidirectional"))
      (node (ref "R52") (pin "1") (pinfunction "1_1") (pintype "passive"))
    )
    (net (code "95") (name "L52") (class "Default")
      (node (ref "B27") (pin "P$2") (pinfunction "K1_P$2") (pintype "bidirectional"))
      (node (ref "B27ALT") (pin "P$2") (pinfunction "K1_P$2") (pintype "bidirectional"))
      (node (ref "R51") (pin "1") (pinfunction "1_1") (pintype "passive"))
    )
    (net (code "96") (name "L53") (class "Default")
      (node (ref "B27") (pin "P$3") (pinfunction "K2_P$3") (pintype "bidirectional"))
      (node (ref "B27ALT") (pin "P$3") (pinfunction "K2_P$3") (pintype "bidirectional"))
      (node (ref "R50") (pin "1") (pinfunction "1_1") (pintype "passive"))
    )
    (net (code "97") (name "L54") (class "Default")
      (node (ref "B28") (pin "P$2") (pinfunction "K1_P$2") (pintype "bidirectional"))
      (node (ref "B28ALT") (pin "P$2") (pinfunction "K1_P$2") (pintype "bidirectional"))
      (node (ref "R49") (pin "1") (pinfunction "1_1") (pintype "passive"))
    )
    (net (code "98") (name "L55") (class "Default")
      (node (ref "B28") (pin "P$3") (pinfunction "K2_P$3") (pintype "bidirectional"))
      (node (ref "B28ALT") (pin "P$3") (pinfunction "K2_P$3") (pintype "bidirectional"))
      (node (ref "R48") (pin "1") (pinfunction "1_1") (pintype "passive"))
    )
    (net (code "99") (name "L56") (class "Default")
      (node (ref "B29") (pin "P$2") (pinfunction "K1_P$2") (pintype "bidirectional"))
      (node (ref "B29ALT") (pin "P$2") (pinfunction "K1_P$2") (pintype "bidirectional"))
      (node (ref "R47") (pin "1") (pinfunction "1_1") (pintype "passive"))
    )
    (net (code "100") (name "L57") (class "Default")
      (node (ref "B29") (pin "P$3") (pinfunction "K2_P$3") (pintype "bidirectional"))
      (node (ref "B29ALT") (pin "P$3") (pinfunction "K2_P$3") (pintype "bidirectional"))
      (node (ref "R46") (pin "1") (pinfunction "1_1") (pintype "passive"))
    )
    (net (code "101") (name "L58") (class "Default")
      (node (ref "B30") (pin "P$2") (pinfunction "K1_P$2") (pintype "bidirectional"))
      (node (ref "B30ALT") (pin "P$2") (pinfunction "K1_P$2") (pintype "bidirectional"))
      (node (ref "R45") (pin "1") (pinfunction "1_1") (pintype "passive"))
    )
    (net (code "102") (name "L59") (class "Default")
      (node (ref "B30") (pin "P$3") (pinfunction "K2_P$3") (pintype "bidirectional"))
      (node (ref "B30ALT") (pin "P$3") (pinfunction "K2_P$3") (pintype "bidirectional"))
      (node (ref "R44") (pin "1") (pinfunction "1_1") (pintype "passive"))
    )
    (net (code "103") (name "L60") (class "Default")
      (node (ref "B31") (pin "P$2") (pinfunction "K1_P$2") (pintype "bidirectional"))
      (node (ref "B31ALT") (pin "P$2") (pinfunction "K1_P$2") (pintype "bidirectional"))
      (node (ref "R43") (pin "1") (pinfunction "1_1") (pintype "passive"))
    )
    (net (code "104") (name "L61") (class "Default")
      (node (ref "B31") (pin "P$3") (pinfunction "K2_P$3") (pintype "bidirectional"))
      (node (ref "B31ALT") (pin "P$3") (pinfunction "K2_P$3") (pintype "bidirectional"))
      (node (ref "R42") (pin "1") (pinfunction "1_1") (pintype "passive"))
    )
    (net (code "105") (name "L62") (class "Default")
      (node (ref "B32") (pin "P$2") (pinfunction "K1_P$2") (pintype "bidirectional"))
      (node (ref "B32ALT") (pin "P$2") (pinfunction "K1_P$2") (pintype "bidirectional"))
      (node (ref "R41") (pin "1") (pinfunction "1_1") (pintype "passive"))
    )
    (net (code "106") (name "L63") (class "Default")
      (node (ref "B32") (pin "P$3") (pinfunction "K2_P$3") (pintype "bidirectional"))
      (node (ref "B32ALT") (pin "P$3") (pinfunction "K2_P$3") (pintype "bidirectional"))
      (node (ref "R40") (pin "1") (pinfunction "1_1") (pintype "passive"))
    )
    (net (code "107") (name "MISO") (class "Default")
      (node (ref "JP1") (pin "3") (pinfunction "3_3") (pintype "passive"))
      (node (ref "U$17") (pin "16") (pinfunction "PB4(PCINT4/MISO)_16") (pintype "bidirectional"))
    )
    (net (code "108") (name "MOSI") (class "Default")
      (node (ref "JP1") (pin "2") (pinfunction "2_2") (pintype "passive"))
      (node (ref "SERIAL") (pin "8") (pinfunction "8_8") (pintype "passive"))
      (node (ref "SSW1") (pin "6") (pinfunction "SDI_6") (pintype "bidirectional"))
      (node (ref "U$17") (pin "15") (pinfunction "PB3(PCINT3/MOSI)_15") (pintype "bidirectional"))
      (node (ref "U$94") (pin "P$8") (pinfunction "8_P$8") (pintype "passive"))
    )
    (net (code "109") (name "Net-(IC2-L0)") (class "Default")
      (node (ref "IC2") (pin "6") (pinfunction "L0_6") (pintype "output"))
      (node (ref "R20") (pin "2") (pinfunction "2_2") (pintype "passive"))
    )
    (net (code "110") (name "Net-(IC2-L1)") (class "Default")
      (node (ref "IC2") (pin "7") (pinfunction "L1_7") (pintype "output"))
      (node (ref "R19") (pin "2") (pinfunction "2_2") (pintype "passive"))
    )
    (net (code "111") (name "Net-(IC2-L2)") (class "Default")
      (node (ref "IC2") (pin "8") (pinfunction "L2_8") (pintype "output"))
      (node (ref "R18") (pin "2") (pinfunction "2_2") (pintype "passive"))
    )
    (net (code "112") (name "Net-(IC2-L3)") (class "Default")
      (node (ref "IC2") (pin "9") (pinfunction "L3_9") (pintype "output"))
      (node (ref "R17") (pin "2") (pinfunction "2_2") (pintype "passive"))
    )
    (net (code "113") (name "Net-(IC2-L4)") (class "Default")
      (node (ref "IC2") (pin "10") (pinfunction "L4_10") (pintype "output"))
      (node (ref "R16") (pin "2") (pinfunction "2_2") (pintype "passive"))
    )
    (net (code "114") (name "Net-(IC2-L5)") (class "Default")
      (node (ref "IC2") (pin "11") (pinfunction "L5_11") (pintype "output"))
      (node (ref "R15") (pin "2") (pinfunction "2_2") (pintype "passive"))
    )
    (net (code "115") (name "Net-(IC2-L6)") (class "Default")
      (node (ref "IC2") (pin "12") (pinfunction "L6_12") (pintype "output"))
      (node (ref "R14") (pin "2") (pinfunction "2_2") (pintype "passive"))
    )
    (net (code "116") (name "Net-(IC2-L7)") (class "Default")
      (node (ref "IC2") (pin "13") (pinfunction "L7_13") (pintype "output"))
      (node (ref "R13") (pin "2") (pinfunction "2_2") (pintype "passive"))
    )
    (net (code "117") (name "Net-(IC2-L8)") (class "Default")
      (node (ref "IC2") (pin "15") (pinfunction "L8_15") (pintype "output"))
      (node (ref "R12") (pin "2") (pinfunction "2_2") (pintype "passive"))
    )
    (net (code "118") (name "Net-(IC2-L9)") (class "Default")
      (node (ref "IC2") (pin "16") (pinfunction "L9_16") (pintype "output"))
      (node (ref "R11") (pin "2") (pinfunction "2_2") (pintype "passive"))
    )
    (net (code "119") (name "Net-(IC2-L10)") (class "Default")
      (node (ref "IC2") (pin "17") (pinfunction "L10_17") (pintype "output"))
      (node (ref "R10") (pin "2") (pinfunction "2_2") (pintype "passive"))
    )
    (net (code "120") (name "Net-(IC2-L11)") (class "Default")
      (node (ref "IC2") (pin "18") (pinfunction "L11_18") (pintype "output"))
      (node (ref "R9") (pin "2") (pinfunction "2_2") (pintype "passive"))
    )
    (net (code "121") (name "Net-(IC2-L12)") (class "Default")
      (node (ref "IC2") (pin "19") (pinfunction "L12_19") (pintype "output"))
      (node (ref "R8") (pin "2") (pinfunction "2_2") (pintype "passive"))
    )
    (net (code "122") (name "Net-(IC2-L13)") (class "Default")
      (node (ref "IC2") (pin "20") (pinfunction "L13_20") (pintype "output"))
      (node (ref "R7") (pin "2") (pinfunction "2_2") (pintype "passive"))
    )
    (net (code "123") (name "Net-(IC2-L14)") (class "Default")
      (node (ref "IC2") (pin "21") (pinfunction "L14_21") (pintype "output"))
      (node (ref "R6") (pin "2") (pinfunction "2_2") (pintype "passive"))
    )
    (net (code "124") (name "Net-(IC2-L15)") (class "Default")
      (node (ref "IC2") (pin "22") (pinfunction "L15_22") (pintype "output"))
      (node (ref "R5") (pin "2") (pinfunction "2_2") (pintype "passive"))
    )
    (net (code "125") (name "Net-(IC3-L0)") (class "Default")
      (node (ref "IC3") (pin "6") (pinfunction "L0_6") (pintype "output"))
      (node (ref "R32") (pin "2") (pinfunction "2_2") (pintype "passive"))
    )
    (net (code "126") (name "Net-(IC3-L1)") (class "Default")
      (node (ref "IC3") (pin "7") (pinfunction "L1_7") (pintype "output"))
      (node (ref "R31") (pin "2") (pinfunction "2_2") (pintype "passive"))
    )
    (net (code "127") (name "Net-(IC3-L2)") (class "Default")
      (node (ref "IC3") (pin "8") (pinfunction "L2_8") (pintype "output"))
      (node (ref "R30") (pin "2") (pinfunction "2_2") (pintype "passive"))
    )
    (net (code "128") (name "Net-(IC3-L3)") (class "Default")
      (node (ref "IC3") (pin "9") (pinfunction "L3_9") (pintype "output"))
      (node (ref "R29") (pin "2") (pinfunction "2_2") (pintype "passive"))
    )
    (net (code "129") (name "Net-(IC3-L4)") (class "Default")
      (node (ref "IC3") (pin "10") (pinfunction "L4_10") (pintype "output"))
      (node (ref "R28") (pin "2") (pinfunction "2_2") (pintype "passive"))
    )
    (net (code "130") (name "Net-(IC3-L5)") (class "Default")
      (node (ref "IC3") (pin "11") (pinfunction "L5_11") (pintype "output"))
      (node (ref "R27") (pin "2") (pinfunction "2_2") (pintype "passive"))
    )
    (net (code "131") (name "Net-(IC3-L6)") (class "Default")
      (node (ref "IC3") (pin "12") (pinfunction "L6_12") (pintype "output"))
      (node (ref "R57") (pin "2") (pinfunction "2_2") (pintype "passive"))
    )
    (net (code "132") (name "Net-(IC3-L7)") (class "Default")
      (node (ref "IC3") (pin "13") (pinfunction "L7_13") (pintype "output"))
      (node (ref "R56") (pin "2") (pinfunction "2_2") (pintype "passive"))
    )
    (net (code "133") (name "Net-(IC3-L8)") (class "Default")
      (node (ref "IC3") (pin "15") (pinfunction "L8_15") (pintype "output"))
      (node (ref "R63") (pin "2") (pinfunction "2_2") (pintype "passive"))
    )
    (net (code "134") (name "Net-(IC3-L9)") (class "Default")
      (node (ref "IC3") (pin "16") (pinfunction "L9_16") (pintype "output"))
      (node (ref "R62") (pin "2") (pinfunction "2_2") (pintype "passive"))
    )
    (net (code "135") (name "Net-(IC3-L10)") (class "Default")
      (node (ref "IC3") (pin "17") (pinfunction "L10_17") (pintype "output"))
      (node (ref "R61") (pin "2") (pinfunction "2_2") (pintype "passive"))
    )
    (net (code "136") (name "Net-(IC3-L11)") (class "Default")
      (node (ref "IC3") (pin "18") (pinfunction "L11_18") (pintype "output"))
      (node (ref "R60") (pin "2") (pinfunction "2_2") (pintype "passive"))
    )
    (net (code "137") (name "Net-(IC3-L12)") (class "Default")
      (node (ref "IC3") (pin "19") (pinfunction "L12_19") (pintype "output"))
      (node (ref "R59") (pin "2") (pinfunction "2_2") (pintype "passive"))
    )
    (net (code "138") (name "Net-(IC3-L13)") (class "Default")
      (node (ref "IC3") (pin "20") (pinfunction "L13_20") (pintype "output"))
      (node (ref "R58") (pin "2") (pinfunction "2_2") (pintype "passive"))
    )
    (net (code "139") (name "Net-(IC3-L14)") (class "Default")
      (node (ref "IC3") (pin "21") (pinfunction "L14_21") (pintype "output"))
      (node (ref "R65") (pin "2") (pinfunction "2_2") (pintype "passive"))
    )
    (net (code "140") (name "Net-(IC3-L15)") (class "Default")
      (node (ref "IC3") (pin "22") (pinfunction "L15_22") (pintype "output"))
      (node (ref "R64") (pin "2") (pinfunction "2_2") (pintype "passive"))
    )
    (net (code "141") (name "Net-(IC6-L0)") (class "Default")
      (node (ref "IC6") (pin "6") (pinfunction "L0_6") (pintype "output"))
      (node (ref "R39") (pin "2") (pinfunction "2_2") (pintype "passive"))
    )
    (net (code "142") (name "Net-(IC6-L1)") (class "Default")
      (node (ref "IC6") (pin "7") (pinfunction "L1_7") (pintype "output"))
      (node (ref "R38") (pin "2") (pinfunction "2_2") (pintype "passive"))
    )
    (net (code "143") (name "Net-(IC6-L2)") (class "Default")
      (node (ref "IC6") (pin "8") (pinfunction "L2_8") (pintype "output"))
      (node (ref "R37") (pin "2") (pinfunction "2_2") (pintype "passive"))
    )
    (net (code "144") (name "Net-(IC6-L3)") (class "Default")
      (node (ref "IC6") (pin "9") (pinfunction "L3_9") (pintype "output"))
      (node (ref "R36") (pin "2") (pinfunction "2_2") (pintype "passive"))
    )
    (net (code "145") (name "Net-(IC6-L4)") (class "Default")
      (node (ref "IC6") (pin "10") (pinfunction "L4_10") (pintype "output"))
      (node (ref "R35") (pin "2") (pinfunction "2_2") (pintype "passive"))
    )
    (net (code "146") (name "Net-(IC6-L5)") (class "Default")
      (node (ref "IC6") (pin "11") (pinfunction "L5_11") (pintype "output"))
      (node (ref "R34") (pin "2") (pinfunction "2_2") (pintype "passive"))
    )
    (net (code "147") (name "Net-(IC6-L6)") (class "Default")
      (node (ref "IC6") (pin "12") (pinfunction "L6_12") (pintype "output"))
      (node (ref "R26") (pin "2") (pinfunction "2_2") (pintype "passive"))
    )
    (net (code "148") (name "Net-(IC6-L7)") (class "Default")
      (node (ref "IC6") (pin "13") (pinfunction "L7_13") (pintype "output"))
      (node (ref "R25") (pin "2") (pinfunction "2_2") (pintype "passive"))
    )
    (net (code "149") (name "Net-(IC6-L8)") (class "Default")
      (node (ref "IC6") (pin "15") (pinfunction "L8_15") (pintype "output"))
      (node (ref "R24") (pin "2") (pinfunction "2_2") (pintype "passive"))
    )
    (net (code "150") (name "Net-(IC6-L9)") (class "Default")
      (node (ref "IC6") (pin "16") (pinfunction "L9_16") (pintype "output"))
      (node (ref "R23") (pin "2") (pinfunction "2_2") (pintype "passive"))
    )
    (net (code "151") (name "Net-(IC6-L10)") (class "Default")
      (node (ref "IC6") (pin "17") (pinfunction "L10_17") (pintype "output"))
      (node (ref "R22") (pin "2") (pinfunction "2_2") (pintype "passive"))
    )
    (net (code "152") (name "Net-(IC6-L11)") (class "Default")
      (node (ref "IC6") (pin "18") (pinfunction "L11_18") (pintype "output"))
      (node (ref "R21") (pin "2") (pinfunction "2_2") (pintype "passive"))
    )
    (net (code "153") (name "Net-(IC6-L12)") (class "Default")
      (node (ref "IC6") (pin "19") (pinfunction "L12_19") (pintype "output"))
      (node (ref "R4") (pin "2") (pinfunction "2_2") (pintype "passive"))
    )
    (net (code "154") (name "Net-(IC6-L13)") (class "Default")
      (node (ref "IC6") (pin "20") (pinfunction "L13_20") (pintype "output"))
      (node (ref "R3") (pin "2") (pinfunction "2_2") (pintype "passive"))
    )
    (net (code "155") (name "Net-(IC6-L14)") (class "Default")
      (node (ref "IC6") (pin "21") (pinfunction "L14_21") (pintype "output"))
      (node (ref "R2") (pin "2") (pinfunction "2_2") (pintype "passive"))
    )
    (net (code "156") (name "Net-(IC6-L15)") (class "Default")
      (node (ref "IC6") (pin "22") (pinfunction "L15_22") (pintype "output"))
      (node (ref "R1") (pin "2") (pinfunction "2_2") (pintype "passive"))
    )
    (net (code "157") (name "Net-(IC8-L0)") (class "Default")
      (node (ref "IC8") (pin "6") (pinfunction "L0_6") (pintype "output"))
      (node (ref "R55") (pin "2") (pinfunction "2_2") (pintype "passive"))
    )
    (net (code "158") (name "Net-(IC8-L1)") (class "Default")
      (node (ref "IC8") (pin "7") (pinfunction "L1_7") (pintype "output"))
      (node (ref "R54") (pin "2") (pinfunction "2_2") (pintype "passive"))
    )
    (net (code "159") (name "Net-(IC8-L2)") (class "Default")
      (node (ref "IC8") (pin "8") (pinfunction "L2_8") (pintype "output"))
      (node (ref "R53") (pin "2") (pinfunction "2_2") (pintype "passive"))
    )
    (net (code "160") (name "Net-(IC8-L3)") (class "Default")
      (node (ref "IC8") (pin "9") (pinfunction "L3_9") (pintype "output"))
      (node (ref "R52") (pin "2") (pinfunction "2_2") (pintype "passive"))
    )
    (net (code "161") (name "Net-(IC8-L4)") (class "Default")
      (node (ref "IC8") (pin "10") (pinfunction "L4_10") (pintype "output"))
      (node (ref "R51") (pin "2") (pinfunction "2_2") (pintype "passive"))
    )
    (net (code "162") (name "Net-(IC8-L5)") (class "Default")
      (node (ref "IC8") (pin "11") (pinfunction "L5_11") (pintype "output"))
      (node (ref "R50") (pin "2") (pinfunction "2_2") (pintype "passive"))
    )
    (net (code "163") (name "Net-(IC8-L6)") (class "Default")
      (node (ref "IC8") (pin "12") (pinfunction "L6_12") (pintype "output"))
      (node (ref "R49") (pin "2") (pinfunction "2_2") (pintype "passive"))
    )
    (net (code "164") (name "Net-(IC8-L7)") (class "Default")
      (node (ref "IC8") (pin "13") (pinfunction "L7_13") (pintype "output"))
      (node (ref "R48") (pin "2") (pinfunction "2_2") (pintype "passive"))
    )
    (net (code "165") (name "Net-(IC8-L8)") (class "Default")
      (node (ref "IC8") (pin "15") (pinfunction "L8_15") (pintype "output"))
      (node (ref "R47") (pin "2") (pinfunction "2_2") (pintype "passive"))
    )
    (net (code "166") (name "Net-(IC8-L9)") (class "Default")
      (node (ref "IC8") (pin "16") (pinfunction "L9_16") (pintype "output"))
      (node (ref "R46") (pin "2") (pinfunction "2_2") (pintype "passive"))
    )
    (net (code "167") (name "Net-(IC8-L10)") (class "Default")
      (node (ref "IC8") (pin "17") (pinfunction "L10_17") (pintype "output"))
      (node (ref "R45") (pin "2") (pinfunction "2_2") (pintype "passive"))
    )
    (net (code "168") (name "Net-(IC8-L11)") (class "Default")
      (node (ref "IC8") (pin "18") (pinfunction "L11_18") (pintype "output"))
      (node (ref "R44") (pin "2") (pinfunction "2_2") (pintype "passive"))
    )
    (net (code "169") (name "Net-(IC8-L12)") (class "Default")
      (node (ref "IC8") (pin "19") (pinfunction "L12_19") (pintype "output"))
      (node (ref "R43") (pin "2") (pinfunction "2_2") (pintype "passive"))
    )
    (net (code "170") (name "Net-(IC8-L13)") (class "Default")
      (node (ref "IC8") (pin "20") (pinfunction "L13_20") (pintype "output"))
      (node (ref "R42") (pin "2") (pinfunction "2_2") (pintype "passive"))
    )
    (net (code "171") (name "Net-(IC8-L14)") (class "Default")
      (node (ref "IC8") (pin "21") (pinfunction "L14_21") (pintype "output"))
      (node (ref "R41") (pin "2") (pinfunction "2_2") (pintype "passive"))
    )
    (net (code "172") (name "Net-(IC8-L15)") (class "Default")
      (node (ref "IC8") (pin "22") (pinfunction "L15_22") (pintype "output"))
      (node (ref "R40") (pin "2") (pinfunction "2_2") (pintype "passive"))
    )
    (net (code "173") (name "Net-(SERIAL-Pad5)") (class "Default")
      (node (ref "SERIAL") (pin "5") (pinfunction "5_5") (pintype "passive"))
      (node (ref "SJ1") (pin "2") (pinfunction "2_2") (pintype "passive"))
    )
    (net (code "174") (name "Net-(U$17-AVCC)") (class "Default")
      (node (ref "C20") (pin "1") (pinfunction "1_1") (pintype "passive"))
      (node (ref "L1") (pin "2") (pinfunction "2_2") (pintype "passive"))
      (node (ref "U$17") (pin "18") (pinfunction "AVCC_18") (pintype "power_in"))
    )
    (net (code "175") (name "RESET") (class "Default")
      (node (ref "JP1") (pin "5") (pinfunction "5_5") (pintype "passive"))
      (node (ref "R33") (pin "1") (pinfunction "1_1") (pintype "passive"))
      (node (ref "U$17") (pin "29") (pinfunction "PC6(RESET/PCINT14)_29") (pintype "bidirectional"))
    )
    (net (code "176") (name "SCLK") (class "Default")
      (node (ref "JP1") (pin "4") (pinfunction "4_4") (pintype "passive"))
      (node (ref "SERIAL") (pin "7") (pinfunction "7_7") (pintype "passive"))
      (node (ref "SSW1") (pin "7") (pinfunction "SCK_7") (pintype "bidirectional"))
      (node (ref "U$17") (pin "17") (pinfunction "PB5(SCK/PCINT5)_17") (pintype "bidirectional"))
      (node (ref "U$94") (pin "P$7") (pinfunction "7_P$7") (pintype "passive"))
    )
    (net (code "177") (name "unconnected-(IC1-INTA-Pad20)") (class "Default")
      (node (ref "IC1") (pin "20") (pinfunction "INTA_20") (pintype "output"))
    )
    (net (code "178") (name "unconnected-(IC1-INTB-Pad19)") (class "Default")
      (node (ref "IC1") (pin "19") (pinfunction "INTB_19") (pintype "output"))
    )
    (net (code "179") (name "unconnected-(IC7-INTA-Pad20)") (class "Default")
      (node (ref "IC7") (pin "20") (pinfunction "INTA_20") (pintype "output"))
    )
    (net (code "180") (name "unconnected-(IC7-INTB-Pad19)") (class "Default")
      (node (ref "IC7") (pin "19") (pinfunction "INTB_19") (pintype "output"))
    )
    (net (code "181") (name "unconnected-(SERIAL-Pad6)") (class "Default")
      (node (ref "SERIAL") (pin "6") (pinfunction "6_6") (pintype "passive"))
    )
    (net (code "182") (name "unconnected-(SSW1-SDO-Pad5)") (class "Default")
      (node (ref "SSW1") (pin "5") (pinfunction "SDO_5") (pintype "bidirectional"))
    )
    (net (code "183") (name "unconnected-(U$17-PA2(PCINT26)-Pad3)") (class "Default")
      (node (ref "U$17") (pin "3") (pinfunction "PA2(PCINT26)_3") (pintype "bidirectional"))
    )
    (net (code "184") (name "unconnected-(U$17-PA3(PCINT27)-Pad6)") (class "Default")
      (node (ref "U$17") (pin "6") (pinfunction "PA3(PCINT27)_6") (pintype "bidirectional"))
    )
    (net (code "185") (name "unconnected-(U$17-PB0(PCINT0{slash}CLK0{slash}ICP1)-Pad12)") (class "Default")
      (node (ref "U$17") (pin "12") (pinfunction "PB0(PCINT0/CLK0/ICP1)_12") (pintype "bidirectional"))
    )
    (net (code "186") (name "unconnected-(U$17-PB1(PCINT1{slash}OC1A)-Pad13)") (class "Default")
      (node (ref "U$17") (pin "13") (pinfunction "PB1(PCINT1/OC1A)_13") (pintype "bidirectional"))
    )
    (net (code "187") (name "unconnected-(U$17-PB2(PCINT2{slash}SS{slash}OC1B)-Pad14)") (class "Default")
      (node (ref "U$17") (pin "14") (pinfunction "PB2(PCINT2/SS/OC1B)_14") (pintype "bidirectional"))
    )
    (net (code "188") (name "unconnected-(U$17-PB6(PCINT6{slash}CLKI)-Pad7)") (class "Default")
      (node (ref "U$17") (pin "7") (pinfunction "PB6(PCINT6/CLKI)_7") (pintype "bidirectional"))
    )
    (net (code "189") (name "unconnected-(U$17-PB7(PCINT7)-Pad8)") (class "Default")
      (node (ref "U$17") (pin "8") (pinfunction "PB7(PCINT7)_8") (pintype "bidirectional"))
    )
    (net (code "190") (name "unconnected-(U$17-PC3(ADC3{slash}PCINT11)-Pad26)") (class "Default")
      (node (ref "U$17") (pin "26") (pinfunction "PC3(ADC3/PCINT11)_26") (pintype "bidirectional"))
    )
    (net (code "191") (name "unconnected-(U$17-PC7(PCINT15)-Pad20)") (class "Default")
      (node (ref "U$17") (pin "20") (pinfunction "PC7(PCINT15)_20") (pintype "bidirectional"))
    )
    (net (code "192") (name "unconnected-(U$17-PD3(INT1{slash}PCINT19)-Pad1)") (class "Default")
      (node (ref "U$17") (pin "1") (pinfunction "PD3(INT1/PCINT19)_1") (pintype "bidirectional"))
    )
    (net (code "193") (name "unconnected-(U$17-PD4(PCINT20{slash}T0)-Pad2)") (class "Default")
      (node (ref "U$17") (pin "2") (pinfunction "PD4(PCINT20/T0)_2") (pintype "bidirectional"))
    )
    (net (code "194") (name "unconnected-(U$17-PD5(PCINT21{slash}T1)-Pad9)") (class "Default")
      (node (ref "U$17") (pin "9") (pinfunction "PD5(PCINT21/T1)_9") (pintype "bidirectional"))
    )
    (net (code "195") (name "unconnected-(U$17-PD7(PCINT23{slash}AIN1)-Pad11)") (class "Default")
      (node (ref "U$17") (pin "11") (pinfunction "PD7(PCINT23/AIN1)_11") (pintype "bidirectional"))
    )
    (net (code "196") (name "unconnected-(U$94-5-PadP$5)") (class "Default")
      (node (ref "U$94") (pin "P$5") (pinfunction "5_P$5") (pintype "passive"))
    )
    (net (code "197") (name "unconnected-(U$94-6-PadP$6)") (class "Default")
      (node (ref "U$94") (pin "P$6") (pinfunction "6_P$6") (pintype "passive"))
    )
  )
)
